# ST_SYS_Board_FPGA.net
KiCad netlist of a schematic drawn in Altium Designer
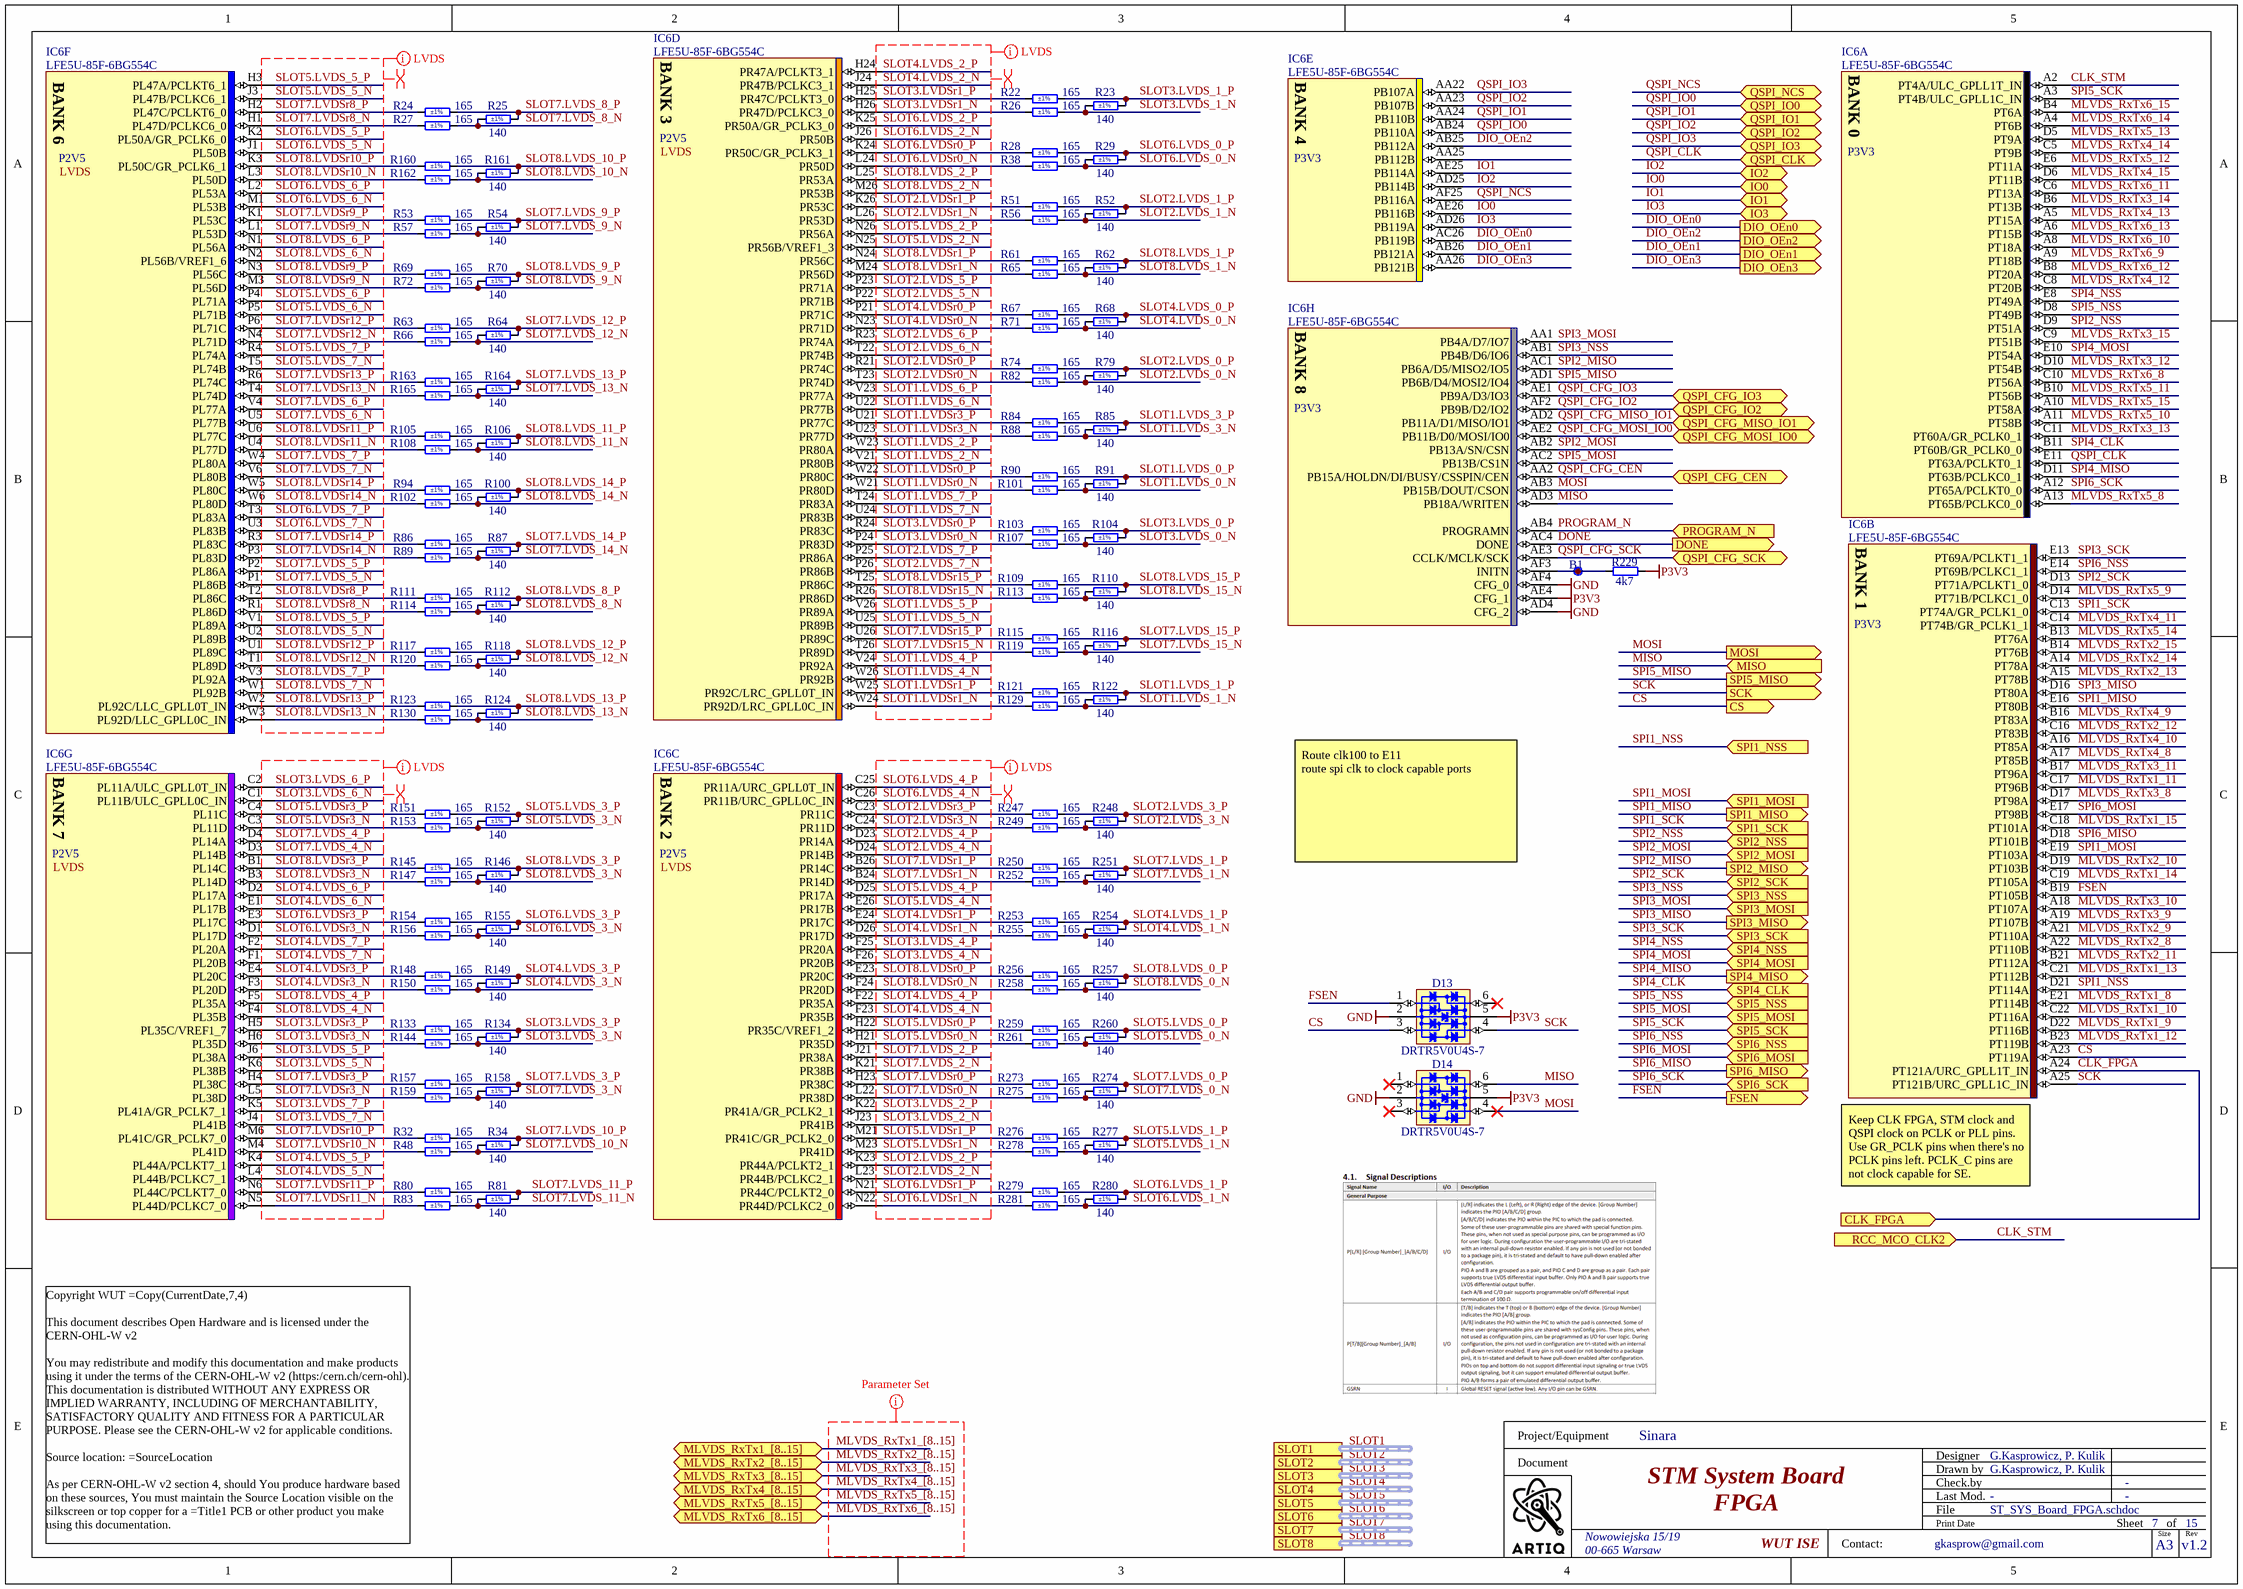
[diagram p0: ST_SYS_Board_FPGA.schdoc]

(export (version "E")
  (design (tool "Eeschema 10.0.6"))
  (components
    (comp (ref "B1")
      (value "SMD Pad")
      (footprint "C75")
      (description "Through Hole Pad")
      (fields (field (name "PART NUMBER") "SMD_PAD_D0.75MM") (field (name "AUTHOR") "CERN DEM BC"))
      (libsource (lib "Eletro-mechanical") (part "Single SMD Pad (Round)"))
    )
    (comp (ref "D13")
      (value "DRTR5V0U4S-7")
      (footprint "SOT65P210X110-6N")
      (description "Integrated Quad Ultra-Low Capacitance ESD Protection")
      (fields (field (name "MANUFACTURER") "DIODES") (field (name "AUTHOR") "GK"))
      (libsource (lib "Diodes") (part "D_TVS_DRTR5V0U4S-7"))
    )
    (comp (ref "D14")
      (value "DRTR5V0U4S-7")
      (footprint "SOT65P210X110-6N")
      (description "Integrated Quad Ultra-Low Capacitance ESD Protection")
      (fields (field (name "MANUFACTURER") "DIODES") (field (name "AUTHOR") "GK"))
      (libsource (lib "Diodes") (part "D_TVS_DRTR5V0U4S-7"))
    )
    (comp (ref "IC6")
      (value "LFE5U-85F-6BG554C")
      (footprint "BGA554C80P26X26_2300X2300X176")
      (fields (field (name "MANUFACTURER") "LATTICE SEMICONDUCTOR") (field (name "AUTHOR") "CERN DEM HF"))
      (libsource (lib "ICs And Semiconductors") (part "LFE5U-85F-6BG554C"))
    )
    (comp (ref "R22")
      (value "165")
      (footprint "RESC0603X28N")
      (description "Resistor - 1%")
      (fields
        (field (name "TOLERANCE") "±1%")
        (field (name "PART NUMBER") "R0201_165R_1%_0.05W_200PPM")
        (field (name "POWER") "0.05W")
        (field (name "AUTHOR") "CERN DEM MR")
      )
      (libsource (lib "Resistors") (part "Resistor - 1%"))
    )
    (comp (ref "R23")
      (value "140")
      (footprint "RESC0603X28N")
      (description "Resistor - 1%")
      (fields
        (field (name "TOLERANCE") "±1%")
        (field (name "PART NUMBER") "R0201_140R_1%_0.05W_200PPM")
        (field (name "POWER") "0.05W")
        (field (name "AUTHOR") "CERN DEM MR")
      )
      (libsource (lib "Resistors") (part "Resistor - 1%"))
    )
    (comp (ref "R24")
      (value "165")
      (footprint "RESC0603X28N")
      (description "Resistor - 1%")
      (fields
        (field (name "TOLERANCE") "±1%")
        (field (name "PART NUMBER") "R0201_165R_1%_0.05W_200PPM")
        (field (name "POWER") "0.05W")
        (field (name "AUTHOR") "CERN DEM MR")
      )
      (libsource (lib "Resistors") (part "Resistor - 1%"))
    )
    (comp (ref "R25")
      (value "140")
      (footprint "RESC0603X28N")
      (description "Resistor - 1%")
      (fields
        (field (name "TOLERANCE") "±1%")
        (field (name "PART NUMBER") "R0201_140R_1%_0.05W_200PPM")
        (field (name "POWER") "0.05W")
        (field (name "AUTHOR") "CERN DEM MR")
      )
      (libsource (lib "Resistors") (part "Resistor - 1%"))
    )
    (comp (ref "R26")
      (value "165")
      (footprint "RESC0603X28N")
      (description "Resistor - 1%")
      (fields
        (field (name "TOLERANCE") "±1%")
        (field (name "PART NUMBER") "R0201_165R_1%_0.05W_200PPM")
        (field (name "POWER") "0.05W")
        (field (name "AUTHOR") "CERN DEM MR")
      )
      (libsource (lib "Resistors") (part "Resistor - 1%"))
    )
    (comp (ref "R27")
      (value "165")
      (footprint "RESC0603X28N")
      (description "Resistor - 1%")
      (fields
        (field (name "TOLERANCE") "±1%")
        (field (name "PART NUMBER") "R0201_165R_1%_0.05W_200PPM")
        (field (name "POWER") "0.05W")
        (field (name "AUTHOR") "CERN DEM MR")
      )
      (libsource (lib "Resistors") (part "Resistor - 1%"))
    )
    (comp (ref "R28")
      (value "165")
      (footprint "RESC0603X28N")
      (description "Resistor - 1%")
      (fields
        (field (name "TOLERANCE") "±1%")
        (field (name "PART NUMBER") "R0201_165R_1%_0.05W_200PPM")
        (field (name "POWER") "0.05W")
        (field (name "AUTHOR") "CERN DEM MR")
      )
      (libsource (lib "Resistors") (part "Resistor - 1%"))
    )
    (comp (ref "R29")
      (value "140")
      (footprint "RESC0603X28N")
      (description "Resistor - 1%")
      (fields
        (field (name "TOLERANCE") "±1%")
        (field (name "PART NUMBER") "R0201_140R_1%_0.05W_200PPM")
        (field (name "POWER") "0.05W")
        (field (name "AUTHOR") "CERN DEM MR")
      )
      (libsource (lib "Resistors") (part "Resistor - 1%"))
    )
    (comp (ref "R32")
      (value "165")
      (footprint "RESC0603X28N")
      (description "Resistor - 1%")
      (fields
        (field (name "TOLERANCE") "±1%")
        (field (name "PART NUMBER") "R0201_165R_1%_0.05W_200PPM")
        (field (name "POWER") "0.05W")
        (field (name "AUTHOR") "CERN DEM MR")
      )
      (libsource (lib "Resistors") (part "Resistor - 1%"))
    )
    (comp (ref "R34")
      (value "140")
      (footprint "RESC0603X28N")
      (description "Resistor - 1%")
      (fields
        (field (name "TOLERANCE") "±1%")
        (field (name "PART NUMBER") "R0201_140R_1%_0.05W_200PPM")
        (field (name "POWER") "0.05W")
        (field (name "AUTHOR") "CERN DEM MR")
      )
      (libsource (lib "Resistors") (part "Resistor - 1%"))
    )
    (comp (ref "R38")
      (value "165")
      (footprint "RESC0603X28N")
      (description "Resistor - 1%")
      (fields
        (field (name "TOLERANCE") "±1%")
        (field (name "PART NUMBER") "R0201_165R_1%_0.05W_200PPM")
        (field (name "POWER") "0.05W")
        (field (name "AUTHOR") "CERN DEM MR")
      )
      (libsource (lib "Resistors") (part "Resistor - 1%"))
    )
    (comp (ref "R48")
      (value "165")
      (footprint "RESC0603X28N")
      (description "Resistor - 1%")
      (fields
        (field (name "TOLERANCE") "±1%")
        (field (name "PART NUMBER") "R0201_165R_1%_0.05W_200PPM")
        (field (name "POWER") "0.05W")
        (field (name "AUTHOR") "CERN DEM MR")
      )
      (libsource (lib "Resistors") (part "Resistor - 1%"))
    )
    (comp (ref "R51")
      (value "165")
      (footprint "RESC0603X28N")
      (description "Resistor - 1%")
      (fields
        (field (name "TOLERANCE") "±1%")
        (field (name "PART NUMBER") "R0201_165R_1%_0.05W_200PPM")
        (field (name "POWER") "0.05W")
        (field (name "AUTHOR") "CERN DEM MR")
      )
      (libsource (lib "Resistors") (part "Resistor - 1%"))
    )
    (comp (ref "R52")
      (value "140")
      (footprint "RESC0603X28N")
      (description "Resistor - 1%")
      (fields
        (field (name "TOLERANCE") "±1%")
        (field (name "PART NUMBER") "R0201_140R_1%_0.05W_200PPM")
        (field (name "POWER") "0.05W")
        (field (name "AUTHOR") "CERN DEM MR")
      )
      (libsource (lib "Resistors") (part "Resistor - 1%"))
    )
    (comp (ref "R53")
      (value "165")
      (footprint "RESC0603X28N")
      (description "Resistor - 1%")
      (fields
        (field (name "TOLERANCE") "±1%")
        (field (name "PART NUMBER") "R0201_165R_1%_0.05W_200PPM")
        (field (name "POWER") "0.05W")
        (field (name "AUTHOR") "CERN DEM MR")
      )
      (libsource (lib "Resistors") (part "Resistor - 1%"))
    )
    (comp (ref "R54")
      (value "140")
      (footprint "RESC0603X28N")
      (description "Resistor - 1%")
      (fields
        (field (name "TOLERANCE") "±1%")
        (field (name "PART NUMBER") "R0201_140R_1%_0.05W_200PPM")
        (field (name "POWER") "0.05W")
        (field (name "AUTHOR") "CERN DEM MR")
      )
      (libsource (lib "Resistors") (part "Resistor - 1%"))
    )
    (comp (ref "R56")
      (value "165")
      (footprint "RESC0603X28N")
      (description "Resistor - 1%")
      (fields
        (field (name "TOLERANCE") "±1%")
        (field (name "PART NUMBER") "R0201_165R_1%_0.05W_200PPM")
        (field (name "POWER") "0.05W")
        (field (name "AUTHOR") "CERN DEM MR")
      )
      (libsource (lib "Resistors") (part "Resistor - 1%"))
    )
    (comp (ref "R57")
      (value "165")
      (footprint "RESC0603X28N")
      (description "Resistor - 1%")
      (fields
        (field (name "TOLERANCE") "±1%")
        (field (name "PART NUMBER") "R0201_165R_1%_0.05W_200PPM")
        (field (name "POWER") "0.05W")
        (field (name "AUTHOR") "CERN DEM MR")
      )
      (libsource (lib "Resistors") (part "Resistor - 1%"))
    )
    (comp (ref "R61")
      (value "165")
      (footprint "RESC0603X28N")
      (description "Resistor - 1%")
      (fields
        (field (name "TOLERANCE") "±1%")
        (field (name "PART NUMBER") "R0201_165R_1%_0.05W_200PPM")
        (field (name "POWER") "0.05W")
        (field (name "AUTHOR") "CERN DEM MR")
      )
      (libsource (lib "Resistors") (part "Resistor - 1%"))
    )
    (comp (ref "R62")
      (value "140")
      (footprint "RESC0603X28N")
      (description "Resistor - 1%")
      (fields
        (field (name "TOLERANCE") "±1%")
        (field (name "PART NUMBER") "R0201_140R_1%_0.05W_200PPM")
        (field (name "POWER") "0.05W")
        (field (name "AUTHOR") "CERN DEM MR")
      )
      (libsource (lib "Resistors") (part "Resistor - 1%"))
    )
    (comp (ref "R63")
      (value "165")
      (footprint "RESC0603X28N")
      (description "Resistor - 1%")
      (fields
        (field (name "TOLERANCE") "±1%")
        (field (name "PART NUMBER") "R0201_165R_1%_0.05W_200PPM")
        (field (name "POWER") "0.05W")
        (field (name "AUTHOR") "CERN DEM MR")
      )
      (libsource (lib "Resistors") (part "Resistor - 1%"))
    )
    (comp (ref "R64")
      (value "140")
      (footprint "RESC0603X28N")
      (description "Resistor - 1%")
      (fields
        (field (name "TOLERANCE") "±1%")
        (field (name "PART NUMBER") "R0201_140R_1%_0.05W_200PPM")
        (field (name "POWER") "0.05W")
        (field (name "AUTHOR") "CERN DEM MR")
      )
      (libsource (lib "Resistors") (part "Resistor - 1%"))
    )
    (comp (ref "R65")
      (value "165")
      (footprint "RESC0603X28N")
      (description "Resistor - 1%")
      (fields
        (field (name "TOLERANCE") "±1%")
        (field (name "PART NUMBER") "R0201_165R_1%_0.05W_200PPM")
        (field (name "POWER") "0.05W")
        (field (name "AUTHOR") "CERN DEM MR")
      )
      (libsource (lib "Resistors") (part "Resistor - 1%"))
    )
    (comp (ref "R66")
      (value "165")
      (footprint "RESC0603X28N")
      (description "Resistor - 1%")
      (fields
        (field (name "TOLERANCE") "±1%")
        (field (name "PART NUMBER") "R0201_165R_1%_0.05W_200PPM")
        (field (name "POWER") "0.05W")
        (field (name "AUTHOR") "CERN DEM MR")
      )
      (libsource (lib "Resistors") (part "Resistor - 1%"))
    )
    (comp (ref "R67")
      (value "165")
      (footprint "RESC0603X28N")
      (description "Resistor - 1%")
      (fields
        (field (name "TOLERANCE") "±1%")
        (field (name "PART NUMBER") "R0201_165R_1%_0.05W_200PPM")
        (field (name "POWER") "0.05W")
        (field (name "AUTHOR") "CERN DEM MR")
      )
      (libsource (lib "Resistors") (part "Resistor - 1%"))
    )
    (comp (ref "R68")
      (value "140")
      (footprint "RESC0603X28N")
      (description "Resistor - 1%")
      (fields
        (field (name "TOLERANCE") "±1%")
        (field (name "PART NUMBER") "R0201_140R_1%_0.05W_200PPM")
        (field (name "POWER") "0.05W")
        (field (name "AUTHOR") "CERN DEM MR")
      )
      (libsource (lib "Resistors") (part "Resistor - 1%"))
    )
    (comp (ref "R69")
      (value "165")
      (footprint "RESC0603X28N")
      (description "Resistor - 1%")
      (fields
        (field (name "TOLERANCE") "±1%")
        (field (name "PART NUMBER") "R0201_165R_1%_0.05W_200PPM")
        (field (name "POWER") "0.05W")
        (field (name "AUTHOR") "CERN DEM MR")
      )
      (libsource (lib "Resistors") (part "Resistor - 1%"))
    )
    (comp (ref "R70")
      (value "140")
      (footprint "RESC0603X28N")
      (description "Resistor - 1%")
      (fields
        (field (name "TOLERANCE") "±1%")
        (field (name "PART NUMBER") "R0201_140R_1%_0.05W_200PPM")
        (field (name "POWER") "0.05W")
        (field (name "AUTHOR") "CERN DEM MR")
      )
      (libsource (lib "Resistors") (part "Resistor - 1%"))
    )
    (comp (ref "R71")
      (value "165")
      (footprint "RESC0603X28N")
      (description "Resistor - 1%")
      (fields
        (field (name "TOLERANCE") "±1%")
        (field (name "PART NUMBER") "R0201_165R_1%_0.05W_200PPM")
        (field (name "POWER") "0.05W")
        (field (name "AUTHOR") "CERN DEM MR")
      )
      (libsource (lib "Resistors") (part "Resistor - 1%"))
    )
    (comp (ref "R72")
      (value "165")
      (footprint "RESC0603X28N")
      (description "Resistor - 1%")
      (fields
        (field (name "TOLERANCE") "±1%")
        (field (name "PART NUMBER") "R0201_165R_1%_0.05W_200PPM")
        (field (name "POWER") "0.05W")
        (field (name "AUTHOR") "CERN DEM MR")
      )
      (libsource (lib "Resistors") (part "Resistor - 1%"))
    )
    (comp (ref "R74")
      (value "165")
      (footprint "RESC0603X28N")
      (description "Resistor - 1%")
      (fields
        (field (name "TOLERANCE") "±1%")
        (field (name "PART NUMBER") "R0201_165R_1%_0.05W_200PPM")
        (field (name "POWER") "0.05W")
        (field (name "AUTHOR") "CERN DEM MR")
      )
      (libsource (lib "Resistors") (part "Resistor - 1%"))
    )
    (comp (ref "R79")
      (value "140")
      (footprint "RESC0603X28N")
      (description "Resistor - 1%")
      (fields
        (field (name "TOLERANCE") "±1%")
        (field (name "PART NUMBER") "R0201_140R_1%_0.05W_200PPM")
        (field (name "POWER") "0.05W")
        (field (name "AUTHOR") "CERN DEM MR")
      )
      (libsource (lib "Resistors") (part "Resistor - 1%"))
    )
    (comp (ref "R80")
      (value "165")
      (footprint "RESC0603X28N")
      (description "Resistor - 1%")
      (fields
        (field (name "TOLERANCE") "±1%")
        (field (name "PART NUMBER") "R0201_165R_1%_0.05W_200PPM")
        (field (name "POWER") "0.05W")
        (field (name "AUTHOR") "CERN DEM MR")
      )
      (libsource (lib "Resistors") (part "Resistor - 1%"))
    )
    (comp (ref "R81")
      (value "140")
      (footprint "RESC0603X28N")
      (description "Resistor - 1%")
      (fields
        (field (name "TOLERANCE") "±1%")
        (field (name "PART NUMBER") "R0201_140R_1%_0.05W_200PPM")
        (field (name "POWER") "0.05W")
        (field (name "AUTHOR") "CERN DEM MR")
      )
      (libsource (lib "Resistors") (part "Resistor - 1%"))
    )
    (comp (ref "R82")
      (value "165")
      (footprint "RESC0603X28N")
      (description "Resistor - 1%")
      (fields
        (field (name "TOLERANCE") "±1%")
        (field (name "PART NUMBER") "R0201_165R_1%_0.05W_200PPM")
        (field (name "POWER") "0.05W")
        (field (name "AUTHOR") "CERN DEM MR")
      )
      (libsource (lib "Resistors") (part "Resistor - 1%"))
    )
    (comp (ref "R83")
      (value "165")
      (footprint "RESC0603X28N")
      (description "Resistor - 1%")
      (fields
        (field (name "TOLERANCE") "±1%")
        (field (name "PART NUMBER") "R0201_165R_1%_0.05W_200PPM")
        (field (name "POWER") "0.05W")
        (field (name "AUTHOR") "CERN DEM MR")
      )
      (libsource (lib "Resistors") (part "Resistor - 1%"))
    )
    (comp (ref "R84")
      (value "165")
      (footprint "RESC0603X28N")
      (description "Resistor - 1%")
      (fields
        (field (name "TOLERANCE") "±1%")
        (field (name "PART NUMBER") "R0201_165R_1%_0.05W_200PPM")
        (field (name "POWER") "0.05W")
        (field (name "AUTHOR") "CERN DEM MR")
      )
      (libsource (lib "Resistors") (part "Resistor - 1%"))
    )
    (comp (ref "R85")
      (value "140")
      (footprint "RESC0603X28N")
      (description "Resistor - 1%")
      (fields
        (field (name "TOLERANCE") "±1%")
        (field (name "PART NUMBER") "R0201_140R_1%_0.05W_200PPM")
        (field (name "POWER") "0.05W")
        (field (name "AUTHOR") "CERN DEM MR")
      )
      (libsource (lib "Resistors") (part "Resistor - 1%"))
    )
    (comp (ref "R86")
      (value "165")
      (footprint "RESC0603X28N")
      (description "Resistor - 1%")
      (fields
        (field (name "TOLERANCE") "±1%")
        (field (name "PART NUMBER") "R0201_165R_1%_0.05W_200PPM")
        (field (name "POWER") "0.05W")
        (field (name "AUTHOR") "CERN DEM MR")
      )
      (libsource (lib "Resistors") (part "Resistor - 1%"))
    )
    (comp (ref "R87")
      (value "140")
      (footprint "RESC0603X28N")
      (description "Resistor - 1%")
      (fields
        (field (name "TOLERANCE") "±1%")
        (field (name "PART NUMBER") "R0201_140R_1%_0.05W_200PPM")
        (field (name "POWER") "0.05W")
        (field (name "AUTHOR") "CERN DEM MR")
      )
      (libsource (lib "Resistors") (part "Resistor - 1%"))
    )
    (comp (ref "R88")
      (value "165")
      (footprint "RESC0603X28N")
      (description "Resistor - 1%")
      (fields
        (field (name "TOLERANCE") "±1%")
        (field (name "PART NUMBER") "R0201_165R_1%_0.05W_200PPM")
        (field (name "POWER") "0.05W")
        (field (name "AUTHOR") "CERN DEM MR")
      )
      (libsource (lib "Resistors") (part "Resistor - 1%"))
    )
    (comp (ref "R89")
      (value "165")
      (footprint "RESC0603X28N")
      (description "Resistor - 1%")
      (fields
        (field (name "TOLERANCE") "±1%")
        (field (name "PART NUMBER") "R0201_165R_1%_0.05W_200PPM")
        (field (name "POWER") "0.05W")
        (field (name "AUTHOR") "CERN DEM MR")
      )
      (libsource (lib "Resistors") (part "Resistor - 1%"))
    )
    (comp (ref "R90")
      (value "165")
      (footprint "RESC0603X28N")
      (description "Resistor - 1%")
      (fields
        (field (name "TOLERANCE") "±1%")
        (field (name "PART NUMBER") "R0201_165R_1%_0.05W_200PPM")
        (field (name "POWER") "0.05W")
        (field (name "AUTHOR") "CERN DEM MR")
      )
      (libsource (lib "Resistors") (part "Resistor - 1%"))
    )
    (comp (ref "R91")
      (value "140")
      (footprint "RESC0603X28N")
      (description "Resistor - 1%")
      (fields
        (field (name "TOLERANCE") "±1%")
        (field (name "PART NUMBER") "R0201_140R_1%_0.05W_200PPM")
        (field (name "POWER") "0.05W")
        (field (name "AUTHOR") "CERN DEM MR")
      )
      (libsource (lib "Resistors") (part "Resistor - 1%"))
    )
    (comp (ref "R94")
      (value "165")
      (footprint "RESC0603X28N")
      (description "Resistor - 1%")
      (fields
        (field (name "TOLERANCE") "±1%")
        (field (name "PART NUMBER") "R0201_165R_1%_0.05W_200PPM")
        (field (name "POWER") "0.05W")
        (field (name "AUTHOR") "CERN DEM MR")
      )
      (libsource (lib "Resistors") (part "Resistor - 1%"))
    )
    (comp (ref "R100")
      (value "140")
      (footprint "RESC0603X28N")
      (description "Resistor - 1%")
      (fields
        (field (name "TOLERANCE") "±1%")
        (field (name "PART NUMBER") "R0201_140R_1%_0.05W_200PPM")
        (field (name "POWER") "0.05W")
        (field (name "AUTHOR") "CERN DEM MR")
      )
      (libsource (lib "Resistors") (part "Resistor - 1%"))
    )
    (comp (ref "R101")
      (value "165")
      (footprint "RESC0603X28N")
      (description "Resistor - 1%")
      (fields
        (field (name "TOLERANCE") "±1%")
        (field (name "PART NUMBER") "R0201_165R_1%_0.05W_200PPM")
        (field (name "POWER") "0.05W")
        (field (name "AUTHOR") "CERN DEM MR")
      )
      (libsource (lib "Resistors") (part "Resistor - 1%"))
    )
    (comp (ref "R102")
      (value "165")
      (footprint "RESC0603X28N")
      (description "Resistor - 1%")
      (fields
        (field (name "TOLERANCE") "±1%")
        (field (name "PART NUMBER") "R0201_165R_1%_0.05W_200PPM")
        (field (name "POWER") "0.05W")
        (field (name "AUTHOR") "CERN DEM MR")
      )
      (libsource (lib "Resistors") (part "Resistor - 1%"))
    )
    (comp (ref "R103")
      (value "165")
      (footprint "RESC0603X28N")
      (description "Resistor - 1%")
      (fields
        (field (name "TOLERANCE") "±1%")
        (field (name "PART NUMBER") "R0201_165R_1%_0.05W_200PPM")
        (field (name "POWER") "0.05W")
        (field (name "AUTHOR") "CERN DEM MR")
      )
      (libsource (lib "Resistors") (part "Resistor - 1%"))
    )
    (comp (ref "R104")
      (value "140")
      (footprint "RESC0603X28N")
      (description "Resistor - 1%")
      (fields
        (field (name "TOLERANCE") "±1%")
        (field (name "PART NUMBER") "R0201_140R_1%_0.05W_200PPM")
        (field (name "POWER") "0.05W")
        (field (name "AUTHOR") "CERN DEM MR")
      )
      (libsource (lib "Resistors") (part "Resistor - 1%"))
    )
    (comp (ref "R105")
      (value "165")
      (footprint "RESC0603X28N")
      (description "Resistor - 1%")
      (fields
        (field (name "TOLERANCE") "±1%")
        (field (name "PART NUMBER") "R0201_165R_1%_0.05W_200PPM")
        (field (name "POWER") "0.05W")
        (field (name "AUTHOR") "CERN DEM MR")
      )
      (libsource (lib "Resistors") (part "Resistor - 1%"))
    )
    (comp (ref "R106")
      (value "140")
      (footprint "RESC0603X28N")
      (description "Resistor - 1%")
      (fields
        (field (name "TOLERANCE") "±1%")
        (field (name "PART NUMBER") "R0201_140R_1%_0.05W_200PPM")
        (field (name "POWER") "0.05W")
        (field (name "AUTHOR") "CERN DEM MR")
      )
      (libsource (lib "Resistors") (part "Resistor - 1%"))
    )
    (comp (ref "R107")
      (value "165")
      (footprint "RESC0603X28N")
      (description "Resistor - 1%")
      (fields
        (field (name "TOLERANCE") "±1%")
        (field (name "PART NUMBER") "R0201_165R_1%_0.05W_200PPM")
        (field (name "POWER") "0.05W")
        (field (name "AUTHOR") "CERN DEM MR")
      )
      (libsource (lib "Resistors") (part "Resistor - 1%"))
    )
    (comp (ref "R108")
      (value "165")
      (footprint "RESC0603X28N")
      (description "Resistor - 1%")
      (fields
        (field (name "TOLERANCE") "±1%")
        (field (name "PART NUMBER") "R0201_165R_1%_0.05W_200PPM")
        (field (name "POWER") "0.05W")
        (field (name "AUTHOR") "CERN DEM MR")
      )
      (libsource (lib "Resistors") (part "Resistor - 1%"))
    )
    (comp (ref "R109")
      (value "165")
      (footprint "RESC0603X28N")
      (description "Resistor - 1%")
      (fields
        (field (name "TOLERANCE") "±1%")
        (field (name "PART NUMBER") "R0201_165R_1%_0.05W_200PPM")
        (field (name "POWER") "0.05W")
        (field (name "AUTHOR") "CERN DEM MR")
      )
      (libsource (lib "Resistors") (part "Resistor - 1%"))
    )
    (comp (ref "R110")
      (value "140")
      (footprint "RESC0603X28N")
      (description "Resistor - 1%")
      (fields
        (field (name "TOLERANCE") "±1%")
        (field (name "PART NUMBER") "R0201_140R_1%_0.05W_200PPM")
        (field (name "POWER") "0.05W")
        (field (name "AUTHOR") "CERN DEM MR")
      )
      (libsource (lib "Resistors") (part "Resistor - 1%"))
    )
    (comp (ref "R111")
      (value "165")
      (footprint "RESC0603X28N")
      (description "Resistor - 1%")
      (fields
        (field (name "TOLERANCE") "±1%")
        (field (name "PART NUMBER") "R0201_165R_1%_0.05W_200PPM")
        (field (name "POWER") "0.05W")
        (field (name "AUTHOR") "CERN DEM MR")
      )
      (libsource (lib "Resistors") (part "Resistor - 1%"))
    )
    (comp (ref "R112")
      (value "140")
      (footprint "RESC0603X28N")
      (description "Resistor - 1%")
      (fields
        (field (name "TOLERANCE") "±1%")
        (field (name "PART NUMBER") "R0201_140R_1%_0.05W_200PPM")
        (field (name "POWER") "0.05W")
        (field (name "AUTHOR") "CERN DEM MR")
      )
      (libsource (lib "Resistors") (part "Resistor - 1%"))
    )
    (comp (ref "R113")
      (value "165")
      (footprint "RESC0603X28N")
      (description "Resistor - 1%")
      (fields
        (field (name "TOLERANCE") "±1%")
        (field (name "PART NUMBER") "R0201_165R_1%_0.05W_200PPM")
        (field (name "POWER") "0.05W")
        (field (name "AUTHOR") "CERN DEM MR")
      )
      (libsource (lib "Resistors") (part "Resistor - 1%"))
    )
    (comp (ref "R114")
      (value "165")
      (footprint "RESC0603X28N")
      (description "Resistor - 1%")
      (fields
        (field (name "TOLERANCE") "±1%")
        (field (name "PART NUMBER") "R0201_165R_1%_0.05W_200PPM")
        (field (name "POWER") "0.05W")
        (field (name "AUTHOR") "CERN DEM MR")
      )
      (libsource (lib "Resistors") (part "Resistor - 1%"))
    )
    (comp (ref "R115")
      (value "165")
      (footprint "RESC0603X28N")
      (description "Resistor - 1%")
      (fields
        (field (name "TOLERANCE") "±1%")
        (field (name "PART NUMBER") "R0201_165R_1%_0.05W_200PPM")
        (field (name "POWER") "0.05W")
        (field (name "AUTHOR") "CERN DEM MR")
      )
      (libsource (lib "Resistors") (part "Resistor - 1%"))
    )
    (comp (ref "R116")
      (value "140")
      (footprint "RESC0603X28N")
      (description "Resistor - 1%")
      (fields
        (field (name "TOLERANCE") "±1%")
        (field (name "PART NUMBER") "R0201_140R_1%_0.05W_200PPM")
        (field (name "POWER") "0.05W")
        (field (name "AUTHOR") "CERN DEM MR")
      )
      (libsource (lib "Resistors") (part "Resistor - 1%"))
    )
    (comp (ref "R117")
      (value "165")
      (footprint "RESC0603X28N")
      (description "Resistor - 1%")
      (fields
        (field (name "TOLERANCE") "±1%")
        (field (name "PART NUMBER") "R0201_165R_1%_0.05W_200PPM")
        (field (name "POWER") "0.05W")
        (field (name "AUTHOR") "CERN DEM MR")
      )
      (libsource (lib "Resistors") (part "Resistor - 1%"))
    )
    (comp (ref "R118")
      (value "140")
      (footprint "RESC0603X28N")
      (description "Resistor - 1%")
      (fields
        (field (name "TOLERANCE") "±1%")
        (field (name "PART NUMBER") "R0201_140R_1%_0.05W_200PPM")
        (field (name "POWER") "0.05W")
        (field (name "AUTHOR") "CERN DEM MR")
      )
      (libsource (lib "Resistors") (part "Resistor - 1%"))
    )
    (comp (ref "R119")
      (value "165")
      (footprint "RESC0603X28N")
      (description "Resistor - 1%")
      (fields
        (field (name "TOLERANCE") "±1%")
        (field (name "PART NUMBER") "R0201_165R_1%_0.05W_200PPM")
        (field (name "POWER") "0.05W")
        (field (name "AUTHOR") "CERN DEM MR")
      )
      (libsource (lib "Resistors") (part "Resistor - 1%"))
    )
    (comp (ref "R120")
      (value "165")
      (footprint "RESC0603X28N")
      (description "Resistor - 1%")
      (fields
        (field (name "TOLERANCE") "±1%")
        (field (name "PART NUMBER") "R0201_165R_1%_0.05W_200PPM")
        (field (name "POWER") "0.05W")
        (field (name "AUTHOR") "CERN DEM MR")
      )
      (libsource (lib "Resistors") (part "Resistor - 1%"))
    )
    (comp (ref "R121")
      (value "165")
      (footprint "RESC0603X28N")
      (description "Resistor - 1%")
      (fields
        (field (name "TOLERANCE") "±1%")
        (field (name "PART NUMBER") "R0201_165R_1%_0.05W_200PPM")
        (field (name "POWER") "0.05W")
        (field (name "AUTHOR") "CERN DEM MR")
      )
      (libsource (lib "Resistors") (part "Resistor - 1%"))
    )
    (comp (ref "R122")
      (value "140")
      (footprint "RESC0603X28N")
      (description "Resistor - 1%")
      (fields
        (field (name "TOLERANCE") "±1%")
        (field (name "PART NUMBER") "R0201_140R_1%_0.05W_200PPM")
        (field (name "POWER") "0.05W")
        (field (name "AUTHOR") "CERN DEM MR")
      )
      (libsource (lib "Resistors") (part "Resistor - 1%"))
    )
    (comp (ref "R123")
      (value "165")
      (footprint "RESC0603X28N")
      (description "Resistor - 1%")
      (fields
        (field (name "TOLERANCE") "±1%")
        (field (name "PART NUMBER") "R0201_165R_1%_0.05W_200PPM")
        (field (name "POWER") "0.05W")
        (field (name "AUTHOR") "CERN DEM MR")
      )
      (libsource (lib "Resistors") (part "Resistor - 1%"))
    )
    (comp (ref "R124")
      (value "140")
      (footprint "RESC0603X28N")
      (description "Resistor - 1%")
      (fields
        (field (name "TOLERANCE") "±1%")
        (field (name "PART NUMBER") "R0201_140R_1%_0.05W_200PPM")
        (field (name "POWER") "0.05W")
        (field (name "AUTHOR") "CERN DEM MR")
      )
      (libsource (lib "Resistors") (part "Resistor - 1%"))
    )
    (comp (ref "R129")
      (value "165")
      (footprint "RESC0603X28N")
      (description "Resistor - 1%")
      (fields
        (field (name "TOLERANCE") "±1%")
        (field (name "PART NUMBER") "R0201_165R_1%_0.05W_200PPM")
        (field (name "POWER") "0.05W")
        (field (name "AUTHOR") "CERN DEM MR")
      )
      (libsource (lib "Resistors") (part "Resistor - 1%"))
    )
    (comp (ref "R130")
      (value "165")
      (footprint "RESC0603X28N")
      (description "Resistor - 1%")
      (fields
        (field (name "TOLERANCE") "±1%")
        (field (name "PART NUMBER") "R0201_165R_1%_0.05W_200PPM")
        (field (name "POWER") "0.05W")
        (field (name "AUTHOR") "CERN DEM MR")
      )
      (libsource (lib "Resistors") (part "Resistor - 1%"))
    )
    (comp (ref "R133")
      (value "165")
      (footprint "RESC0603X28N")
      (description "Resistor - 1%")
      (fields
        (field (name "TOLERANCE") "±1%")
        (field (name "PART NUMBER") "R0201_165R_1%_0.05W_200PPM")
        (field (name "POWER") "0.05W")
        (field (name "AUTHOR") "CERN DEM MR")
      )
      (libsource (lib "Resistors") (part "Resistor - 1%"))
    )
    (comp (ref "R134")
      (value "140")
      (footprint "RESC0603X28N")
      (description "Resistor - 1%")
      (fields
        (field (name "TOLERANCE") "±1%")
        (field (name "PART NUMBER") "R0201_140R_1%_0.05W_200PPM")
        (field (name "POWER") "0.05W")
        (field (name "AUTHOR") "CERN DEM MR")
      )
      (libsource (lib "Resistors") (part "Resistor - 1%"))
    )
    (comp (ref "R144")
      (value "165")
      (footprint "RESC0603X28N")
      (description "Resistor - 1%")
      (fields
        (field (name "TOLERANCE") "±1%")
        (field (name "PART NUMBER") "R0201_165R_1%_0.05W_200PPM")
        (field (name "POWER") "0.05W")
        (field (name "AUTHOR") "CERN DEM MR")
      )
      (libsource (lib "Resistors") (part "Resistor - 1%"))
    )
    (comp (ref "R145")
      (value "165")
      (footprint "RESC0603X28N")
      (description "Resistor - 1%")
      (fields
        (field (name "TOLERANCE") "±1%")
        (field (name "PART NUMBER") "R0201_165R_1%_0.05W_200PPM")
        (field (name "POWER") "0.05W")
        (field (name "AUTHOR") "CERN DEM MR")
      )
      (libsource (lib "Resistors") (part "Resistor - 1%"))
    )
    (comp (ref "R146")
      (value "140")
      (footprint "RESC0603X28N")
      (description "Resistor - 1%")
      (fields
        (field (name "TOLERANCE") "±1%")
        (field (name "PART NUMBER") "R0201_140R_1%_0.05W_200PPM")
        (field (name "POWER") "0.05W")
        (field (name "AUTHOR") "CERN DEM MR")
      )
      (libsource (lib "Resistors") (part "Resistor - 1%"))
    )
    (comp (ref "R147")
      (value "165")
      (footprint "RESC0603X28N")
      (description "Resistor - 1%")
      (fields
        (field (name "TOLERANCE") "±1%")
        (field (name "PART NUMBER") "R0201_165R_1%_0.05W_200PPM")
        (field (name "POWER") "0.05W")
        (field (name "AUTHOR") "CERN DEM MR")
      )
      (libsource (lib "Resistors") (part "Resistor - 1%"))
    )
    (comp (ref "R148")
      (value "165")
      (footprint "RESC0603X28N")
      (description "Resistor - 1%")
      (fields
        (field (name "TOLERANCE") "±1%")
        (field (name "PART NUMBER") "R0201_165R_1%_0.05W_200PPM")
        (field (name "POWER") "0.05W")
        (field (name "AUTHOR") "CERN DEM MR")
      )
      (libsource (lib "Resistors") (part "Resistor - 1%"))
    )
    (comp (ref "R149")
      (value "140")
      (footprint "RESC0603X28N")
      (description "Resistor - 1%")
      (fields
        (field (name "TOLERANCE") "±1%")
        (field (name "PART NUMBER") "R0201_140R_1%_0.05W_200PPM")
        (field (name "POWER") "0.05W")
        (field (name "AUTHOR") "CERN DEM MR")
      )
      (libsource (lib "Resistors") (part "Resistor - 1%"))
    )
    (comp (ref "R150")
      (value "165")
      (footprint "RESC0603X28N")
      (description "Resistor - 1%")
      (fields
        (field (name "TOLERANCE") "±1%")
        (field (name "PART NUMBER") "R0201_165R_1%_0.05W_200PPM")
        (field (name "POWER") "0.05W")
        (field (name "AUTHOR") "CERN DEM MR")
      )
      (libsource (lib "Resistors") (part "Resistor - 1%"))
    )
    (comp (ref "R151")
      (value "165")
      (footprint "RESC0603X28N")
      (description "Resistor - 1%")
      (fields
        (field (name "TOLERANCE") "±1%")
        (field (name "PART NUMBER") "R0201_165R_1%_0.05W_200PPM")
        (field (name "POWER") "0.05W")
        (field (name "AUTHOR") "CERN DEM MR")
      )
      (libsource (lib "Resistors") (part "Resistor - 1%"))
    )
    (comp (ref "R152")
      (value "140")
      (footprint "RESC0603X28N")
      (description "Resistor - 1%")
      (fields
        (field (name "TOLERANCE") "±1%")
        (field (name "PART NUMBER") "R0201_140R_1%_0.05W_200PPM")
        (field (name "POWER") "0.05W")
        (field (name "AUTHOR") "CERN DEM MR")
      )
      (libsource (lib "Resistors") (part "Resistor - 1%"))
    )
    (comp (ref "R153")
      (value "165")
      (footprint "RESC0603X28N")
      (description "Resistor - 1%")
      (fields
        (field (name "TOLERANCE") "±1%")
        (field (name "PART NUMBER") "R0201_165R_1%_0.05W_200PPM")
        (field (name "POWER") "0.05W")
        (field (name "AUTHOR") "CERN DEM MR")
      )
      (libsource (lib "Resistors") (part "Resistor - 1%"))
    )
    (comp (ref "R154")
      (value "165")
      (footprint "RESC0603X28N")
      (description "Resistor - 1%")
      (fields
        (field (name "TOLERANCE") "±1%")
        (field (name "PART NUMBER") "R0201_165R_1%_0.05W_200PPM")
        (field (name "POWER") "0.05W")
        (field (name "AUTHOR") "CERN DEM MR")
      )
      (libsource (lib "Resistors") (part "Resistor - 1%"))
    )
    (comp (ref "R155")
      (value "140")
      (footprint "RESC0603X28N")
      (description "Resistor - 1%")
      (fields
        (field (name "TOLERANCE") "±1%")
        (field (name "PART NUMBER") "R0201_140R_1%_0.05W_200PPM")
        (field (name "POWER") "0.05W")
        (field (name "AUTHOR") "CERN DEM MR")
      )
      (libsource (lib "Resistors") (part "Resistor - 1%"))
    )
    (comp (ref "R156")
      (value "165")
      (footprint "RESC0603X28N")
      (description "Resistor - 1%")
      (fields
        (field (name "TOLERANCE") "±1%")
        (field (name "PART NUMBER") "R0201_165R_1%_0.05W_200PPM")
        (field (name "POWER") "0.05W")
        (field (name "AUTHOR") "CERN DEM MR")
      )
      (libsource (lib "Resistors") (part "Resistor - 1%"))
    )
    (comp (ref "R157")
      (value "165")
      (footprint "RESC0603X28N")
      (description "Resistor - 1%")
      (fields
        (field (name "TOLERANCE") "±1%")
        (field (name "PART NUMBER") "R0201_165R_1%_0.05W_200PPM")
        (field (name "POWER") "0.05W")
        (field (name "AUTHOR") "CERN DEM MR")
      )
      (libsource (lib "Resistors") (part "Resistor - 1%"))
    )
    (comp (ref "R158")
      (value "140")
      (footprint "RESC0603X28N")
      (description "Resistor - 1%")
      (fields
        (field (name "TOLERANCE") "±1%")
        (field (name "PART NUMBER") "R0201_140R_1%_0.05W_200PPM")
        (field (name "POWER") "0.05W")
        (field (name "AUTHOR") "CERN DEM MR")
      )
      (libsource (lib "Resistors") (part "Resistor - 1%"))
    )
    (comp (ref "R159")
      (value "165")
      (footprint "RESC0603X28N")
      (description "Resistor - 1%")
      (fields
        (field (name "TOLERANCE") "±1%")
        (field (name "PART NUMBER") "R0201_165R_1%_0.05W_200PPM")
        (field (name "POWER") "0.05W")
        (field (name "AUTHOR") "CERN DEM MR")
      )
      (libsource (lib "Resistors") (part "Resistor - 1%"))
    )
    (comp (ref "R160")
      (value "165")
      (footprint "RESC0603X28N")
      (description "Resistor - 1%")
      (fields
        (field (name "TOLERANCE") "±1%")
        (field (name "PART NUMBER") "R0201_165R_1%_0.05W_200PPM")
        (field (name "POWER") "0.05W")
        (field (name "AUTHOR") "CERN DEM MR")
      )
      (libsource (lib "Resistors") (part "Resistor - 1%"))
    )
    (comp (ref "R161")
      (value "140")
      (footprint "RESC0603X28N")
      (description "Resistor - 1%")
      (fields
        (field (name "TOLERANCE") "±1%")
        (field (name "PART NUMBER") "R0201_140R_1%_0.05W_200PPM")
        (field (name "POWER") "0.05W")
        (field (name "AUTHOR") "CERN DEM MR")
      )
      (libsource (lib "Resistors") (part "Resistor - 1%"))
    )
    (comp (ref "R162")
      (value "165")
      (footprint "RESC0603X28N")
      (description "Resistor - 1%")
      (fields
        (field (name "TOLERANCE") "±1%")
        (field (name "PART NUMBER") "R0201_165R_1%_0.05W_200PPM")
        (field (name "POWER") "0.05W")
        (field (name "AUTHOR") "CERN DEM MR")
      )
      (libsource (lib "Resistors") (part "Resistor - 1%"))
    )
    (comp (ref "R163")
      (value "165")
      (footprint "RESC0603X28N")
      (description "Resistor - 1%")
      (fields
        (field (name "TOLERANCE") "±1%")
        (field (name "PART NUMBER") "R0201_165R_1%_0.05W_200PPM")
        (field (name "POWER") "0.05W")
        (field (name "AUTHOR") "CERN DEM MR")
      )
      (libsource (lib "Resistors") (part "Resistor - 1%"))
    )
    (comp (ref "R164")
      (value "140")
      (footprint "RESC0603X28N")
      (description "Resistor - 1%")
      (fields
        (field (name "TOLERANCE") "±1%")
        (field (name "PART NUMBER") "R0201_140R_1%_0.05W_200PPM")
        (field (name "POWER") "0.05W")
        (field (name "AUTHOR") "CERN DEM MR")
      )
      (libsource (lib "Resistors") (part "Resistor - 1%"))
    )
    (comp (ref "R165")
      (value "165")
      (footprint "RESC0603X28N")
      (description "Resistor - 1%")
      (fields
        (field (name "TOLERANCE") "±1%")
        (field (name "PART NUMBER") "R0201_165R_1%_0.05W_200PPM")
        (field (name "POWER") "0.05W")
        (field (name "AUTHOR") "CERN DEM MR")
      )
      (libsource (lib "Resistors") (part "Resistor - 1%"))
    )
    (comp (ref "R229")
      (value "4k7")
      (footprint "RESC1005X40N")
      (description "Resistor - 1%")
      (fields
        (field (name "PART NUMBER") "R0402_4K7_1%_0.0625W_100PPM")
        (field (name "POWER") "0.0625W")
        (field (name "AUTHOR") "CERN DEM JLC")
      )
      (libsource (lib "Resistors") (part "Resistor - 1%"))
    )
    (comp (ref "R247")
      (value "165")
      (footprint "RESC0603X28N")
      (description "Resistor - 1%")
      (fields
        (field (name "TOLERANCE") "±1%")
        (field (name "PART NUMBER") "R0201_165R_1%_0.05W_200PPM")
        (field (name "POWER") "0.05W")
        (field (name "AUTHOR") "CERN DEM MR")
      )
      (libsource (lib "Resistors") (part "Resistor - 1%"))
    )
    (comp (ref "R248")
      (value "140")
      (footprint "RESC0603X28N")
      (description "Resistor - 1%")
      (fields
        (field (name "TOLERANCE") "±1%")
        (field (name "PART NUMBER") "R0201_140R_1%_0.05W_200PPM")
        (field (name "POWER") "0.05W")
        (field (name "AUTHOR") "CERN DEM MR")
      )
      (libsource (lib "Resistors") (part "Resistor - 1%"))
    )
    (comp (ref "R249")
      (value "165")
      (footprint "RESC0603X28N")
      (description "Resistor - 1%")
      (fields
        (field (name "TOLERANCE") "±1%")
        (field (name "PART NUMBER") "R0201_165R_1%_0.05W_200PPM")
        (field (name "POWER") "0.05W")
        (field (name "AUTHOR") "CERN DEM MR")
      )
      (libsource (lib "Resistors") (part "Resistor - 1%"))
    )
    (comp (ref "R250")
      (value "165")
      (footprint "RESC0603X28N")
      (description "Resistor - 1%")
      (fields
        (field (name "TOLERANCE") "±1%")
        (field (name "PART NUMBER") "R0201_165R_1%_0.05W_200PPM")
        (field (name "POWER") "0.05W")
        (field (name "AUTHOR") "CERN DEM MR")
      )
      (libsource (lib "Resistors") (part "Resistor - 1%"))
    )
    (comp (ref "R251")
      (value "140")
      (footprint "RESC0603X28N")
      (description "Resistor - 1%")
      (fields
        (field (name "TOLERANCE") "±1%")
        (field (name "PART NUMBER") "R0201_140R_1%_0.05W_200PPM")
        (field (name "POWER") "0.05W")
        (field (name "AUTHOR") "CERN DEM MR")
      )
      (libsource (lib "Resistors") (part "Resistor - 1%"))
    )
    (comp (ref "R252")
      (value "165")
      (footprint "RESC0603X28N")
      (description "Resistor - 1%")
      (fields
        (field (name "TOLERANCE") "±1%")
        (field (name "PART NUMBER") "R0201_165R_1%_0.05W_200PPM")
        (field (name "POWER") "0.05W")
        (field (name "AUTHOR") "CERN DEM MR")
      )
      (libsource (lib "Resistors") (part "Resistor - 1%"))
    )
    (comp (ref "R253")
      (value "165")
      (footprint "RESC0603X28N")
      (description "Resistor - 1%")
      (fields
        (field (name "TOLERANCE") "±1%")
        (field (name "PART NUMBER") "R0201_165R_1%_0.05W_200PPM")
        (field (name "POWER") "0.05W")
        (field (name "AUTHOR") "CERN DEM MR")
      )
      (libsource (lib "Resistors") (part "Resistor - 1%"))
    )
    (comp (ref "R254")
      (value "140")
      (footprint "RESC0603X28N")
      (description "Resistor - 1%")
      (fields
        (field (name "TOLERANCE") "±1%")
        (field (name "PART NUMBER") "R0201_140R_1%_0.05W_200PPM")
        (field (name "POWER") "0.05W")
        (field (name "AUTHOR") "CERN DEM MR")
      )
      (libsource (lib "Resistors") (part "Resistor - 1%"))
    )
    (comp (ref "R255")
      (value "165")
      (footprint "RESC0603X28N")
      (description "Resistor - 1%")
      (fields
        (field (name "TOLERANCE") "±1%")
        (field (name "PART NUMBER") "R0201_165R_1%_0.05W_200PPM")
        (field (name "POWER") "0.05W")
        (field (name "AUTHOR") "CERN DEM MR")
      )
      (libsource (lib "Resistors") (part "Resistor - 1%"))
    )
    (comp (ref "R256")
      (value "165")
      (footprint "RESC0603X28N")
      (description "Resistor - 1%")
      (fields
        (field (name "TOLERANCE") "±1%")
        (field (name "PART NUMBER") "R0201_165R_1%_0.05W_200PPM")
        (field (name "POWER") "0.05W")
        (field (name "AUTHOR") "CERN DEM MR")
      )
      (libsource (lib "Resistors") (part "Resistor - 1%"))
    )
    (comp (ref "R257")
      (value "140")
      (footprint "RESC0603X28N")
      (description "Resistor - 1%")
      (fields
        (field (name "TOLERANCE") "±1%")
        (field (name "PART NUMBER") "R0201_140R_1%_0.05W_200PPM")
        (field (name "POWER") "0.05W")
        (field (name "AUTHOR") "CERN DEM MR")
      )
      (libsource (lib "Resistors") (part "Resistor - 1%"))
    )
    (comp (ref "R258")
      (value "165")
      (footprint "RESC0603X28N")
      (description "Resistor - 1%")
      (fields
        (field (name "TOLERANCE") "±1%")
        (field (name "PART NUMBER") "R0201_165R_1%_0.05W_200PPM")
        (field (name "POWER") "0.05W")
        (field (name "AUTHOR") "CERN DEM MR")
      )
      (libsource (lib "Resistors") (part "Resistor - 1%"))
    )
    (comp (ref "R259")
      (value "165")
      (footprint "RESC0603X28N")
      (description "Resistor - 1%")
      (fields
        (field (name "TOLERANCE") "±1%")
        (field (name "PART NUMBER") "R0201_165R_1%_0.05W_200PPM")
        (field (name "POWER") "0.05W")
        (field (name "AUTHOR") "CERN DEM MR")
      )
      (libsource (lib "Resistors") (part "Resistor - 1%"))
    )
    (comp (ref "R260")
      (value "140")
      (footprint "RESC0603X28N")
      (description "Resistor - 1%")
      (fields
        (field (name "TOLERANCE") "±1%")
        (field (name "PART NUMBER") "R0201_140R_1%_0.05W_200PPM")
        (field (name "POWER") "0.05W")
        (field (name "AUTHOR") "CERN DEM MR")
      )
      (libsource (lib "Resistors") (part "Resistor - 1%"))
    )
    (comp (ref "R261")
      (value "165")
      (footprint "RESC0603X28N")
      (description "Resistor - 1%")
      (fields
        (field (name "TOLERANCE") "±1%")
        (field (name "PART NUMBER") "R0201_165R_1%_0.05W_200PPM")
        (field (name "POWER") "0.05W")
        (field (name "AUTHOR") "CERN DEM MR")
      )
      (libsource (lib "Resistors") (part "Resistor - 1%"))
    )
    (comp (ref "R273")
      (value "165")
      (footprint "RESC0603X28N")
      (description "Resistor - 1%")
      (fields
        (field (name "TOLERANCE") "±1%")
        (field (name "PART NUMBER") "R0201_165R_1%_0.05W_200PPM")
        (field (name "POWER") "0.05W")
        (field (name "AUTHOR") "CERN DEM MR")
      )
      (libsource (lib "Resistors") (part "Resistor - 1%"))
    )
    (comp (ref "R274")
      (value "140")
      (footprint "RESC0603X28N")
      (description "Resistor - 1%")
      (fields
        (field (name "TOLERANCE") "±1%")
        (field (name "PART NUMBER") "R0201_140R_1%_0.05W_200PPM")
        (field (name "POWER") "0.05W")
        (field (name "AUTHOR") "CERN DEM MR")
      )
      (libsource (lib "Resistors") (part "Resistor - 1%"))
    )
    (comp (ref "R275")
      (value "165")
      (footprint "RESC0603X28N")
      (description "Resistor - 1%")
      (fields
        (field (name "TOLERANCE") "±1%")
        (field (name "PART NUMBER") "R0201_165R_1%_0.05W_200PPM")
        (field (name "POWER") "0.05W")
        (field (name "AUTHOR") "CERN DEM MR")
      )
      (libsource (lib "Resistors") (part "Resistor - 1%"))
    )
    (comp (ref "R276")
      (value "165")
      (footprint "RESC0603X28N")
      (description "Resistor - 1%")
      (fields
        (field (name "TOLERANCE") "±1%")
        (field (name "PART NUMBER") "R0201_165R_1%_0.05W_200PPM")
        (field (name "POWER") "0.05W")
        (field (name "AUTHOR") "CERN DEM MR")
      )
      (libsource (lib "Resistors") (part "Resistor - 1%"))
    )
    (comp (ref "R277")
      (value "140")
      (footprint "RESC0603X28N")
      (description "Resistor - 1%")
      (fields
        (field (name "TOLERANCE") "±1%")
        (field (name "PART NUMBER") "R0201_140R_1%_0.05W_200PPM")
        (field (name "POWER") "0.05W")
        (field (name "AUTHOR") "CERN DEM MR")
      )
      (libsource (lib "Resistors") (part "Resistor - 1%"))
    )
    (comp (ref "R278")
      (value "165")
      (footprint "RESC0603X28N")
      (description "Resistor - 1%")
      (fields
        (field (name "TOLERANCE") "±1%")
        (field (name "PART NUMBER") "R0201_165R_1%_0.05W_200PPM")
        (field (name "POWER") "0.05W")
        (field (name "AUTHOR") "CERN DEM MR")
      )
      (libsource (lib "Resistors") (part "Resistor - 1%"))
    )
    (comp (ref "R279")
      (value "165")
      (footprint "RESC0603X28N")
      (description "Resistor - 1%")
      (fields
        (field (name "TOLERANCE") "±1%")
        (field (name "PART NUMBER") "R0201_165R_1%_0.05W_200PPM")
        (field (name "POWER") "0.05W")
        (field (name "AUTHOR") "CERN DEM MR")
      )
      (libsource (lib "Resistors") (part "Resistor - 1%"))
    )
    (comp (ref "R280")
      (value "140")
      (footprint "RESC0603X28N")
      (description "Resistor - 1%")
      (fields
        (field (name "TOLERANCE") "±1%")
        (field (name "PART NUMBER") "R0201_140R_1%_0.05W_200PPM")
        (field (name "POWER") "0.05W")
        (field (name "AUTHOR") "CERN DEM MR")
      )
      (libsource (lib "Resistors") (part "Resistor - 1%"))
    )
    (comp (ref "R281")
      (value "165")
      (footprint "RESC0603X28N")
      (description "Resistor - 1%")
      (fields
        (field (name "TOLERANCE") "±1%")
        (field (name "PART NUMBER") "R0201_165R_1%_0.05W_200PPM")
        (field (name "POWER") "0.05W")
        (field (name "AUTHOR") "CERN DEM MR")
      )
      (libsource (lib "Resistors") (part "Resistor - 1%"))
    )
  )
  (nets
    (net (code "9") (name "/CLK_FPGA") (class "Default")
      (node (ref "IC6") (pin "A24") (pinfunction "PT121A/URC_GPLL1T_IN_A24") (pintype "bidirectional"))
    )
    (net (code "10") (name "/CLK_STM") (class "Default")
      (node (ref "IC6") (pin "A2") (pinfunction "PT4A/ULC_GPLL1T_IN_A2") (pintype "bidirectional"))
    )
    (net (code "11") (name "/CS") (class "Default")
      (node (ref "D13") (pin "3") (pinfunction "I/O2_3") (pintype "bidirectional"))
      (node (ref "IC6") (pin "A23") (pinfunction "PT119A_A23") (pintype "bidirectional"))
    )
    (net (code "12") (name "/DIO_OEn0") (class "Default")
      (node (ref "IC6") (pin "AC26") (pinfunction "PB119B_AC26") (pintype "bidirectional"))
    )
    (net (code "13") (name "/DIO_OEn1") (class "Default")
      (node (ref "IC6") (pin "AB26") (pinfunction "PB121A_AB26") (pintype "bidirectional"))
    )
    (net (code "14") (name "/DIO_OEn2") (class "Default")
      (node (ref "IC6") (pin "AB25") (pinfunction "PB112A_AB25") (pintype "bidirectional"))
    )
    (net (code "15") (name "/DIO_OEn3") (class "Default")
      (node (ref "IC6") (pin "AA26") (pinfunction "PB121B_AA26") (pintype "bidirectional"))
    )
    (net (code "16") (name "/DONE") (class "Default")
      (node (ref "IC6") (pin "AC4") (pinfunction "DONE_AC4") (pintype "bidirectional"))
    )
    (net (code "17") (name "/FSEN") (class "Default")
      (node (ref "D13") (pin "1") (pinfunction "I/O1_1") (pintype "bidirectional"))
      (node (ref "IC6") (pin "B19") (pinfunction "PT105B_B19") (pintype "bidirectional"))
    )
    (net (code "18") (name "/IO0") (class "Default")
      (node (ref "IC6") (pin "AE26") (pinfunction "PB116B_AE26") (pintype "bidirectional"))
    )
    (net (code "19") (name "/IO1") (class "Default")
      (node (ref "IC6") (pin "AE25") (pinfunction "PB114A_AE25") (pintype "bidirectional"))
    )
    (net (code "20") (name "/IO2") (class "Default")
      (node (ref "IC6") (pin "AD25") (pinfunction "PB114B_AD25") (pintype "bidirectional"))
    )
    (net (code "21") (name "/IO3") (class "Default")
      (node (ref "IC6") (pin "AD26") (pinfunction "PB119A_AD26") (pintype "bidirectional"))
    )
    (net (code "22") (name "/MISO") (class "Default")
      (node (ref "D14") (pin "6") (pinfunction "I/O4_6") (pintype "bidirectional"))
      (node (ref "IC6") (pin "AD3") (pinfunction "PB18A/WRITEN_AD3") (pintype "bidirectional"))
    )
    (net (code "23") (name "/MLVDS_RxTx1_8") (class "Default")
      (node (ref "IC6") (pin "E21") (pinfunction "PT114B_E21") (pintype "bidirectional"))
    )
    (net (code "24") (name "/MLVDS_RxTx1_9") (class "Default")
      (node (ref "IC6") (pin "D22") (pinfunction "PT116B_D22") (pintype "bidirectional"))
    )
    (net (code "25") (name "/MLVDS_RxTx1_10") (class "Default")
      (node (ref "IC6") (pin "C22") (pinfunction "PT116A_C22") (pintype "bidirectional"))
    )
    (net (code "26") (name "/MLVDS_RxTx1_11") (class "Default")
      (node (ref "IC6") (pin "C17") (pinfunction "PT96B_C17") (pintype "bidirectional"))
    )
    (net (code "27") (name "/MLVDS_RxTx1_12") (class "Default")
      (node (ref "IC6") (pin "B23") (pinfunction "PT119B_B23") (pintype "bidirectional"))
    )
    (net (code "28") (name "/MLVDS_RxTx1_13") (class "Default")
      (node (ref "IC6") (pin "C21") (pinfunction "PT112B_C21") (pintype "bidirectional"))
    )
    (net (code "29") (name "/MLVDS_RxTx1_14") (class "Default")
      (node (ref "IC6") (pin "C19") (pinfunction "PT105A_C19") (pintype "bidirectional"))
    )
    (net (code "30") (name "/MLVDS_RxTx1_15") (class "Default")
      (node (ref "IC6") (pin "C18") (pinfunction "PT101A_C18") (pintype "bidirectional"))
    )
    (net (code "32") (name "/MLVDS_RxTx2_8") (class "Default")
      (node (ref "IC6") (pin "A22") (pinfunction "PT110B_A22") (pintype "bidirectional"))
    )
    (net (code "33") (name "/MLVDS_RxTx2_9") (class "Default")
      (node (ref "IC6") (pin "A21") (pinfunction "PT110A_A21") (pintype "bidirectional"))
    )
    (net (code "34") (name "/MLVDS_RxTx2_10") (class "Default")
      (node (ref "IC6") (pin "D19") (pinfunction "PT103B_D19") (pintype "bidirectional"))
    )
    (net (code "35") (name "/MLVDS_RxTx2_11") (class "Default")
      (node (ref "IC6") (pin "B21") (pinfunction "PT112A_B21") (pintype "bidirectional"))
    )
    (net (code "36") (name "/MLVDS_RxTx2_12") (class "Default")
      (node (ref "IC6") (pin "C16") (pinfunction "PT83B_C16") (pintype "bidirectional"))
    )
    (net (code "37") (name "/MLVDS_RxTx2_13") (class "Default")
      (node (ref "IC6") (pin "A15") (pinfunction "PT78B_A15") (pintype "bidirectional"))
    )
    (net (code "38") (name "/MLVDS_RxTx2_14") (class "Default")
      (node (ref "IC6") (pin "A14") (pinfunction "PT78A_A14") (pintype "bidirectional"))
    )
    (net (code "39") (name "/MLVDS_RxTx2_15") (class "Default")
      (node (ref "IC6") (pin "B14") (pinfunction "PT76B_B14") (pintype "bidirectional"))
    )
    (net (code "41") (name "/MLVDS_RxTx3_8") (class "Default")
      (node (ref "IC6") (pin "D17") (pinfunction "PT98A_D17") (pintype "bidirectional"))
    )
    (net (code "42") (name "/MLVDS_RxTx3_9") (class "Default")
      (node (ref "IC6") (pin "A19") (pinfunction "PT107B_A19") (pintype "bidirectional"))
    )
    (net (code "43") (name "/MLVDS_RxTx3_10") (class "Default")
      (node (ref "IC6") (pin "A18") (pinfunction "PT107A_A18") (pintype "bidirectional"))
    )
    (net (code "44") (name "/MLVDS_RxTx3_11") (class "Default")
      (node (ref "IC6") (pin "B17") (pinfunction "PT96A_B17") (pintype "bidirectional"))
    )
    (net (code "45") (name "/MLVDS_RxTx3_12") (class "Default")
      (node (ref "IC6") (pin "D10") (pinfunction "PT54B_D10") (pintype "bidirectional"))
    )
    (net (code "46") (name "/MLVDS_RxTx3_13") (class "Default")
      (node (ref "IC6") (pin "C11") (pinfunction "PT60A/GR_PCLK0_1_C11") (pintype "bidirectional"))
    )
    (net (code "47") (name "/MLVDS_RxTx3_14") (class "Default")
      (node (ref "IC6") (pin "B6") (pinfunction "PT13B_B6") (pintype "bidirectional"))
    )
    (net (code "48") (name "/MLVDS_RxTx3_15") (class "Default")
      (node (ref "IC6") (pin "C9") (pinfunction "PT51B_C9") (pintype "bidirectional"))
    )
    (net (code "50") (name "/MLVDS_RxTx4_8") (class "Default")
      (node (ref "IC6") (pin "A17") (pinfunction "PT85B_A17") (pintype "bidirectional"))
    )
    (net (code "51") (name "/MLVDS_RxTx4_9") (class "Default")
      (node (ref "IC6") (pin "B16") (pinfunction "PT83A_B16") (pintype "bidirectional"))
    )
    (net (code "52") (name "/MLVDS_RxTx4_10") (class "Default")
      (node (ref "IC6") (pin "A16") (pinfunction "PT85A_A16") (pintype "bidirectional"))
    )
    (net (code "53") (name "/MLVDS_RxTx4_11") (class "Default")
      (node (ref "IC6") (pin "C14") (pinfunction "PT74B/GR_PCLK1_1_C14") (pintype "bidirectional"))
    )
    (net (code "54") (name "/MLVDS_RxTx4_12") (class "Default")
      (node (ref "IC6") (pin "C8") (pinfunction "PT20B_C8") (pintype "bidirectional"))
    )
    (net (code "55") (name "/MLVDS_RxTx4_13") (class "Default")
      (node (ref "IC6") (pin "A5") (pinfunction "PT15A_A5") (pintype "bidirectional"))
    )
    (net (code "56") (name "/MLVDS_RxTx4_14") (class "Default")
      (node (ref "IC6") (pin "C5") (pinfunction "PT9B_C5") (pintype "bidirectional"))
    )
    (net (code "57") (name "/MLVDS_RxTx4_15") (class "Default")
      (node (ref "IC6") (pin "D6") (pinfunction "PT11B_D6") (pintype "bidirectional"))
    )
    (net (code "59") (name "/MLVDS_RxTx5_8") (class "Default")
      (node (ref "IC6") (pin "A13") (pinfunction "PT65B/PCLKC0_0_A13") (pintype "bidirectional"))
    )
    (net (code "60") (name "/MLVDS_RxTx5_9") (class "Default")
      (node (ref "IC6") (pin "D14") (pinfunction "PT71B/PCLKC1_0_D14") (pintype "bidirectional"))
    )
    (net (code "61") (name "/MLVDS_RxTx5_10") (class "Default")
      (node (ref "IC6") (pin "A11") (pinfunction "PT58B_A11") (pintype "bidirectional"))
    )
    (net (code "62") (name "/MLVDS_RxTx5_11") (class "Default")
      (node (ref "IC6") (pin "B10") (pinfunction "PT56B_B10") (pintype "bidirectional"))
    )
    (net (code "63") (name "/MLVDS_RxTx5_12") (class "Default")
      (node (ref "IC6") (pin "E6") (pinfunction "PT11A_E6") (pintype "bidirectional"))
    )
    (net (code "64") (name "/MLVDS_RxTx5_13") (class "Default")
      (node (ref "IC6") (pin "D5") (pinfunction "PT9A_D5") (pintype "bidirectional"))
    )
    (net (code "65") (name "/MLVDS_RxTx5_14") (class "Default")
      (node (ref "IC6") (pin "B13") (pinfunction "PT76A_B13") (pintype "bidirectional"))
    )
    (net (code "66") (name "/MLVDS_RxTx5_15") (class "Default")
      (node (ref "IC6") (pin "A10") (pinfunction "PT58A_A10") (pintype "bidirectional"))
    )
    (net (code "68") (name "/MLVDS_RxTx6_8") (class "Default")
      (node (ref "IC6") (pin "C10") (pinfunction "PT56A_C10") (pintype "bidirectional"))
    )
    (net (code "69") (name "/MLVDS_RxTx6_9") (class "Default")
      (node (ref "IC6") (pin "A9") (pinfunction "PT18B_A9") (pintype "bidirectional"))
    )
    (net (code "70") (name "/MLVDS_RxTx6_10") (class "Default")
      (node (ref "IC6") (pin "A8") (pinfunction "PT18A_A8") (pintype "bidirectional"))
    )
    (net (code "71") (name "/MLVDS_RxTx6_11") (class "Default")
      (node (ref "IC6") (pin "C6") (pinfunction "PT13A_C6") (pintype "bidirectional"))
    )
    (net (code "72") (name "/MLVDS_RxTx6_12") (class "Default")
      (node (ref "IC6") (pin "B8") (pinfunction "PT20A_B8") (pintype "bidirectional"))
    )
    (net (code "73") (name "/MLVDS_RxTx6_13") (class "Default")
      (node (ref "IC6") (pin "A6") (pinfunction "PT15B_A6") (pintype "bidirectional"))
    )
    (net (code "74") (name "/MLVDS_RxTx6_14") (class "Default")
      (node (ref "IC6") (pin "A4") (pinfunction "PT6B_A4") (pintype "bidirectional"))
    )
    (net (code "75") (name "/MLVDS_RxTx6_15") (class "Default")
      (node (ref "IC6") (pin "B4") (pinfunction "PT6A_B4") (pintype "bidirectional"))
    )
    (net (code "77") (name "/MOSI") (class "Default")
      (node (ref "D14") (pin "4") (pinfunction "I/O3_4") (pintype "bidirectional"))
      (node (ref "IC6") (pin "AB3") (pinfunction "PB15B/DOUT/CSON_AB3") (pintype "bidirectional"))
    )
    (net (code "78") (name "/PROGRAM_N") (class "Default")
      (node (ref "IC6") (pin "AB4") (pinfunction "PROGRAMN_AB4") (pintype "bidirectional"))
    )
    (net (code "79") (name "/QSPI_CFG_CEN") (class "Default")
      (node (ref "IC6") (pin "AA2") (pinfunction "PB15A/HOLDN/DI/BUSY/CSSPIN/CEN_AA2") (pintype "bidirectional"))
    )
    (net (code "80") (name "/QSPI_CFG_IO2") (class "Default")
      (node (ref "IC6") (pin "AF2") (pinfunction "PB9B/D2/IO2_AF2") (pintype "bidirectional"))
    )
    (net (code "81") (name "/QSPI_CFG_IO3") (class "Default")
      (node (ref "IC6") (pin "AE1") (pinfunction "PB9A/D3/IO3_AE1") (pintype "bidirectional"))
    )
    (net (code "82") (name "/QSPI_CFG_MISO_IO1") (class "Default")
      (node (ref "IC6") (pin "AD2") (pinfunction "PB11A/D1/MISO/IO1_AD2") (pintype "bidirectional"))
    )
    (net (code "83") (name "/QSPI_CFG_MOSI_IO0") (class "Default")
      (node (ref "IC6") (pin "AE2") (pinfunction "PB11B/D0/MOSI/IO0_AE2") (pintype "bidirectional"))
    )
    (net (code "84") (name "/QSPI_CFG_SCK") (class "Default")
      (node (ref "IC6") (pin "AE3") (pinfunction "CCLK/MCLK/SCK_AE3") (pintype "bidirectional"))
    )
    (net (code "85") (name "/QSPI_CLK") (class "Default")
      (node (ref "IC6") (pin "E11") (pinfunction "PT63A/PCLKT0_1_E11") (pintype "bidirectional"))
    )
    (net (code "86") (name "/QSPI_IO0") (class "Default")
      (node (ref "IC6") (pin "AB24") (pinfunction "PB110A_AB24") (pintype "bidirectional"))
    )
    (net (code "87") (name "/QSPI_IO1") (class "Default")
      (node (ref "IC6") (pin "AA24") (pinfunction "PB110B_AA24") (pintype "bidirectional"))
    )
    (net (code "88") (name "/QSPI_IO2") (class "Default")
      (node (ref "IC6") (pin "AA23") (pinfunction "PB107B_AA23") (pintype "bidirectional"))
    )
    (net (code "89") (name "/QSPI_IO3") (class "Default")
      (node (ref "IC6") (pin "AA22") (pinfunction "PB107A_AA22") (pintype "bidirectional"))
    )
    (net (code "90") (name "/QSPI_NCS") (class "Default")
      (node (ref "IC6") (pin "AF25") (pinfunction "PB116A_AF25") (pintype "bidirectional"))
    )
    (net (code "91") (name "/SCK") (class "Default")
      (node (ref "D13") (pin "4") (pinfunction "I/O3_4") (pintype "bidirectional"))
      (node (ref "IC6") (pin "A25") (pinfunction "PT121B/URC_GPLL1C_IN_A25") (pintype "bidirectional"))
    )
    (net (code "92") (name "/SLOT1.LVDS_0_N") (class "Default")
      (node (ref "R101") (pin "2") (pinfunction "2_2") (pintype "passive"))
      (node (ref "R91") (pin "1") (pinfunction "1_1") (pintype "passive"))
    )
    (net (code "93") (name "/SLOT1.LVDS_0_P") (class "Default")
      (node (ref "R90") (pin "2") (pinfunction "2_2") (pintype "passive"))
      (node (ref "R91") (pin "2") (pinfunction "2_2") (pintype "passive"))
    )
    (net (code "94") (name "/SLOT1.LVDS_1_N") (class "Default")
      (node (ref "R122") (pin "1") (pinfunction "1_1") (pintype "passive"))
      (node (ref "R129") (pin "2") (pinfunction "2_2") (pintype "passive"))
    )
    (net (code "95") (name "/SLOT1.LVDS_1_P") (class "Default")
      (node (ref "R121") (pin "2") (pinfunction "2_2") (pintype "passive"))
      (node (ref "R122") (pin "2") (pinfunction "2_2") (pintype "passive"))
    )
    (net (code "96") (name "/SLOT1.LVDS_2_N") (class "Default")
      (node (ref "IC6") (pin "V21") (pinfunction "PR80B_V21") (pintype "bidirectional"))
    )
    (net (code "97") (name "/SLOT1.LVDS_2_P") (class "Default")
      (node (ref "IC6") (pin "W23") (pinfunction "PR80A_W23") (pintype "bidirectional"))
    )
    (net (code "98") (name "/SLOT1.LVDS_3_N") (class "Default")
      (node (ref "R85") (pin "1") (pinfunction "1_1") (pintype "passive"))
      (node (ref "R88") (pin "2") (pinfunction "2_2") (pintype "passive"))
    )
    (net (code "99") (name "/SLOT1.LVDS_3_P") (class "Default")
      (node (ref "R84") (pin "2") (pinfunction "2_2") (pintype "passive"))
      (node (ref "R85") (pin "2") (pinfunction "2_2") (pintype "passive"))
    )
    (net (code "100") (name "/SLOT1.LVDS_4_N") (class "Default")
      (node (ref "IC6") (pin "W26") (pinfunction "PR92B_W26") (pintype "bidirectional"))
    )
    (net (code "101") (name "/SLOT1.LVDS_4_P") (class "Default")
      (node (ref "IC6") (pin "V24") (pinfunction "PR92A_V24") (pintype "bidirectional"))
    )
    (net (code "102") (name "/SLOT1.LVDS_5_N") (class "Default")
      (node (ref "IC6") (pin "U25") (pinfunction "PR89B_U25") (pintype "bidirectional"))
    )
    (net (code "103") (name "/SLOT1.LVDS_5_P") (class "Default")
      (node (ref "IC6") (pin "V26") (pinfunction "PR89A_V26") (pintype "bidirectional"))
    )
    (net (code "104") (name "/SLOT1.LVDS_6_N") (class "Default")
      (node (ref "IC6") (pin "U22") (pinfunction "PR77B_U22") (pintype "bidirectional"))
    )
    (net (code "105") (name "/SLOT1.LVDS_6_P") (class "Default")
      (node (ref "IC6") (pin "V23") (pinfunction "PR77A_V23") (pintype "bidirectional"))
    )
    (net (code "106") (name "/SLOT1.LVDS_7_N") (class "Default")
      (node (ref "IC6") (pin "U24") (pinfunction "PR83B_U24") (pintype "bidirectional"))
    )
    (net (code "107") (name "/SLOT1.LVDS_7_P") (class "Default")
      (node (ref "IC6") (pin "T24") (pinfunction "PR83A_T24") (pintype "bidirectional"))
    )
    (net (code "108") (name "/SLOT1.LVDSr0_N") (class "Default")
      (node (ref "IC6") (pin "W21") (pinfunction "PR80D_W21") (pintype "bidirectional"))
      (node (ref "R101") (pin "1") (pinfunction "1_1") (pintype "passive"))
    )
    (net (code "109") (name "/SLOT1.LVDSr0_P") (class "Default")
      (node (ref "IC6") (pin "W22") (pinfunction "PR80C_W22") (pintype "bidirectional"))
      (node (ref "R90") (pin "1") (pinfunction "1_1") (pintype "passive"))
    )
    (net (code "110") (name "/SLOT1.LVDSr1_N") (class "Default")
      (node (ref "IC6") (pin "W24") (pinfunction "PR92D/LRC_GPLL0C_IN_W24") (pintype "bidirectional"))
      (node (ref "R129") (pin "1") (pinfunction "1_1") (pintype "passive"))
    )
    (net (code "111") (name "/SLOT1.LVDSr1_P") (class "Default")
      (node (ref "IC6") (pin "W25") (pinfunction "PR92C/LRC_GPLL0T_IN_W25") (pintype "bidirectional"))
      (node (ref "R121") (pin "1") (pinfunction "1_1") (pintype "passive"))
    )
    (net (code "112") (name "/SLOT1.LVDSr3_N") (class "Default")
      (node (ref "IC6") (pin "U23") (pinfunction "PR77D_U23") (pintype "bidirectional"))
      (node (ref "R88") (pin "1") (pinfunction "1_1") (pintype "passive"))
    )
    (net (code "113") (name "/SLOT1.LVDSr3_P") (class "Default")
      (node (ref "IC6") (pin "U21") (pinfunction "PR77C_U21") (pintype "bidirectional"))
      (node (ref "R84") (pin "1") (pinfunction "1_1") (pintype "passive"))
    )
    (net (code "114") (name "/SLOT2.LVDS_0_N") (class "Default")
      (node (ref "R79") (pin "1") (pinfunction "1_1") (pintype "passive"))
      (node (ref "R82") (pin "2") (pinfunction "2_2") (pintype "passive"))
    )
    (net (code "115") (name "/SLOT2.LVDS_0_P") (class "Default")
      (node (ref "R74") (pin "2") (pinfunction "2_2") (pintype "passive"))
      (node (ref "R79") (pin "2") (pinfunction "2_2") (pintype "passive"))
    )
    (net (code "116") (name "/SLOT2.LVDS_1_N") (class "Default")
      (node (ref "R52") (pin "1") (pinfunction "1_1") (pintype "passive"))
      (node (ref "R56") (pin "2") (pinfunction "2_2") (pintype "passive"))
    )
    (net (code "117") (name "/SLOT2.LVDS_1_P") (class "Default")
      (node (ref "R51") (pin "2") (pinfunction "2_2") (pintype "passive"))
      (node (ref "R52") (pin "2") (pinfunction "2_2") (pintype "passive"))
    )
    (net (code "118") (name "/SLOT2.LVDS_2_N") (class "Default")
      (node (ref "IC6") (pin "L23") (pinfunction "PR44B/PCLKC2_1_L23") (pintype "bidirectional"))
    )
    (net (code "119") (name "/SLOT2.LVDS_2_P") (class "Default")
      (node (ref "IC6") (pin "K23") (pinfunction "PR44A/PCLKT2_1_K23") (pintype "bidirectional"))
    )
    (net (code "120") (name "/SLOT2.LVDS_3_N") (class "Default")
      (node (ref "R248") (pin "1") (pinfunction "1_1") (pintype "passive"))
      (node (ref "R249") (pin "2") (pinfunction "2_2") (pintype "passive"))
    )
    (net (code "121") (name "/SLOT2.LVDS_3_P") (class "Default")
      (node (ref "R247") (pin "2") (pinfunction "2_2") (pintype "passive"))
      (node (ref "R248") (pin "2") (pinfunction "2_2") (pintype "passive"))
    )
    (net (code "122") (name "/SLOT2.LVDS_4_N") (class "Default")
      (node (ref "IC6") (pin "D24") (pinfunction "PR14B_D24") (pintype "bidirectional"))
    )
    (net (code "123") (name "/SLOT2.LVDS_4_P") (class "Default")
      (node (ref "IC6") (pin "D23") (pinfunction "PR14A_D23") (pintype "bidirectional"))
    )
    (net (code "124") (name "/SLOT2.LVDS_5_N") (class "Default")
      (node (ref "IC6") (pin "P22") (pinfunction "PR71B_P22") (pintype "bidirectional"))
    )
    (net (code "125") (name "/SLOT2.LVDS_5_P") (class "Default")
      (node (ref "IC6") (pin "P23") (pinfunction "PR71A_P23") (pintype "bidirectional"))
    )
    (net (code "126") (name "/SLOT2.LVDS_6_N") (class "Default")
      (node (ref "IC6") (pin "T22") (pinfunction "PR74B_T22") (pintype "bidirectional"))
    )
    (net (code "127") (name "/SLOT2.LVDS_6_P") (class "Default")
      (node (ref "IC6") (pin "R23") (pinfunction "PR74A_R23") (pintype "bidirectional"))
    )
    (net (code "128") (name "/SLOT2.LVDS_7_N") (class "Default")
      (node (ref "IC6") (pin "P26") (pinfunction "PR86B_P26") (pintype "bidirectional"))
    )
    (net (code "129") (name "/SLOT2.LVDS_7_P") (class "Default")
      (node (ref "IC6") (pin "P25") (pinfunction "PR86A_P25") (pintype "bidirectional"))
    )
    (net (code "130") (name "/SLOT2.LVDSr0_N") (class "Default")
      (node (ref "IC6") (pin "T23") (pinfunction "PR74D_T23") (pintype "bidirectional"))
      (node (ref "R82") (pin "1") (pinfunction "1_1") (pintype "passive"))
    )
    (net (code "131") (name "/SLOT2.LVDSr0_P") (class "Default")
      (node (ref "IC6") (pin "R21") (pinfunction "PR74C_R21") (pintype "bidirectional"))
      (node (ref "R74") (pin "1") (pinfunction "1_1") (pintype "passive"))
    )
    (net (code "132") (name "/SLOT2.LVDSr1_N") (class "Default")
      (node (ref "IC6") (pin "L26") (pinfunction "PR53D_L26") (pintype "bidirectional"))
      (node (ref "R56") (pin "1") (pinfunction "1_1") (pintype "passive"))
    )
    (net (code "133") (name "/SLOT2.LVDSr1_P") (class "Default")
      (node (ref "IC6") (pin "K26") (pinfunction "PR53C_K26") (pintype "bidirectional"))
      (node (ref "R51") (pin "1") (pinfunction "1_1") (pintype "passive"))
    )
    (net (code "134") (name "/SLOT2.LVDSr3_N") (class "Default")
      (node (ref "IC6") (pin "C24") (pinfunction "PR11D_C24") (pintype "bidirectional"))
      (node (ref "R249") (pin "1") (pinfunction "1_1") (pintype "passive"))
    )
    (net (code "135") (name "/SLOT2.LVDSr3_P") (class "Default")
      (node (ref "IC6") (pin "C23") (pinfunction "PR11C_C23") (pintype "bidirectional"))
      (node (ref "R247") (pin "1") (pinfunction "1_1") (pintype "passive"))
    )
    (net (code "136") (name "/SLOT3.LVDS_0_N") (class "Default")
      (node (ref "R104") (pin "1") (pinfunction "1_1") (pintype "passive"))
      (node (ref "R107") (pin "2") (pinfunction "2_2") (pintype "passive"))
    )
    (net (code "137") (name "/SLOT3.LVDS_0_P") (class "Default")
      (node (ref "R103") (pin "2") (pinfunction "2_2") (pintype "passive"))
      (node (ref "R104") (pin "2") (pinfunction "2_2") (pintype "passive"))
    )
    (net (code "138") (name "/SLOT3.LVDS_1_N") (class "Default")
      (node (ref "R23") (pin "1") (pinfunction "1_1") (pintype "passive"))
      (node (ref "R26") (pin "2") (pinfunction "2_2") (pintype "passive"))
    )
    (net (code "139") (name "/SLOT3.LVDS_1_P") (class "Default")
      (node (ref "R22") (pin "2") (pinfunction "2_2") (pintype "passive"))
      (node (ref "R23") (pin "2") (pinfunction "2_2") (pintype "passive"))
    )
    (net (code "140") (name "/SLOT3.LVDS_2_N") (class "Default")
      (node (ref "IC6") (pin "J23") (pinfunction "PR41B_J23") (pintype "bidirectional"))
    )
    (net (code "141") (name "/SLOT3.LVDS_2_P") (class "Default")
      (node (ref "IC6") (pin "K22") (pinfunction "PR41A/GR_PCLK2_1_K22") (pintype "bidirectional"))
    )
    (net (code "142") (name "/SLOT3.LVDS_3_N") (class "Default")
      (node (ref "R134") (pin "1") (pinfunction "1_1") (pintype "passive"))
      (node (ref "R144") (pin "2") (pinfunction "2_2") (pintype "passive"))
    )
    (net (code "143") (name "/SLOT3.LVDS_3_P") (class "Default")
      (node (ref "R133") (pin "2") (pinfunction "2_2") (pintype "passive"))
      (node (ref "R134") (pin "2") (pinfunction "2_2") (pintype "passive"))
    )
    (net (code "144") (name "/SLOT3.LVDS_4_N") (class "Default")
      (node (ref "IC6") (pin "F26") (pinfunction "PR20B_F26") (pintype "bidirectional"))
    )
    (net (code "145") (name "/SLOT3.LVDS_4_P") (class "Default")
      (node (ref "IC6") (pin "F25") (pinfunction "PR20A_F25") (pintype "bidirectional"))
    )
    (net (code "146") (name "/SLOT3.LVDS_5_N") (class "Default")
      (node (ref "IC6") (pin "K6") (pinfunction "PL38B_K6") (pintype "bidirectional"))
    )
    (net (code "147") (name "/SLOT3.LVDS_5_P") (class "Default")
      (node (ref "IC6") (pin "J6") (pinfunction "PL38A_J6") (pintype "bidirectional"))
    )
    (net (code "148") (name "/SLOT3.LVDS_6_N") (class "Default")
      (node (ref "IC6") (pin "C1") (pinfunction "PL11B/ULC_GPLL0C_IN_C1") (pintype "bidirectional"))
    )
    (net (code "149") (name "/SLOT3.LVDS_6_P") (class "Default")
      (node (ref "IC6") (pin "C2") (pinfunction "PL11A/ULC_GPLL0T_IN_C2") (pintype "bidirectional"))
    )
    (net (code "150") (name "/SLOT3.LVDS_7_N") (class "Default")
      (node (ref "IC6") (pin "J4") (pinfunction "PL41B_J4") (pintype "bidirectional"))
    )
    (net (code "151") (name "/SLOT3.LVDS_7_P") (class "Default")
      (node (ref "IC6") (pin "K5") (pinfunction "PL41A/GR_PCLK7_1_K5") (pintype "bidirectional"))
    )
    (net (code "152") (name "/SLOT3.LVDSr0_N") (class "Default")
      (node (ref "IC6") (pin "P24") (pinfunction "PR83D_P24") (pintype "bidirectional"))
      (node (ref "R107") (pin "1") (pinfunction "1_1") (pintype "passive"))
    )
    (net (code "153") (name "/SLOT3.LVDSr0_P") (class "Default")
      (node (ref "IC6") (pin "R24") (pinfunction "PR83C_R24") (pintype "bidirectional"))
      (node (ref "R103") (pin "1") (pinfunction "1_1") (pintype "passive"))
    )
    (net (code "154") (name "/SLOT3.LVDSr1_N") (class "Default")
      (node (ref "IC6") (pin "H26") (pinfunction "PR47D/PCLKC3_0_H26") (pintype "bidirectional"))
      (node (ref "R26") (pin "1") (pinfunction "1_1") (pintype "passive"))
    )
    (net (code "155") (name "/SLOT3.LVDSr1_P") (class "Default")
      (node (ref "IC6") (pin "H25") (pinfunction "PR47C/PCLKT3_0_H25") (pintype "bidirectional"))
      (node (ref "R22") (pin "1") (pinfunction "1_1") (pintype "passive"))
    )
    (net (code "156") (name "/SLOT3.LVDSr3_N") (class "Default")
      (node (ref "IC6") (pin "H6") (pinfunction "PL35D_H6") (pintype "bidirectional"))
      (node (ref "R144") (pin "1") (pinfunction "1_1") (pintype "passive"))
    )
    (net (code "157") (name "/SLOT3.LVDSr3_P") (class "Default")
      (node (ref "IC6") (pin "H5") (pinfunction "PL35C/VREF1_7_H5") (pintype "bidirectional"))
      (node (ref "R133") (pin "1") (pinfunction "1_1") (pintype "passive"))
    )
    (net (code "158") (name "/SLOT4.LVDS_0_N") (class "Default")
      (node (ref "R68") (pin "1") (pinfunction "1_1") (pintype "passive"))
      (node (ref "R71") (pin "2") (pinfunction "2_2") (pintype "passive"))
    )
    (net (code "159") (name "/SLOT4.LVDS_0_P") (class "Default")
      (node (ref "R67") (pin "2") (pinfunction "2_2") (pintype "passive"))
      (node (ref "R68") (pin "2") (pinfunction "2_2") (pintype "passive"))
    )
    (net (code "160") (name "/SLOT4.LVDS_1_N") (class "Default")
      (node (ref "R254") (pin "1") (pinfunction "1_1") (pintype "passive"))
      (node (ref "R255") (pin "2") (pinfunction "2_2") (pintype "passive"))
    )
    (net (code "161") (name "/SLOT4.LVDS_1_P") (class "Default")
      (node (ref "R253") (pin "2") (pinfunction "2_2") (pintype "passive"))
      (node (ref "R254") (pin "2") (pinfunction "2_2") (pintype "passive"))
    )
    (net (code "162") (name "/SLOT4.LVDS_2_N") (class "Default")
      (node (ref "IC6") (pin "J24") (pinfunction "PR47B/PCLKC3_1_J24") (pintype "bidirectional"))
    )
    (net (code "163") (name "/SLOT4.LVDS_2_P") (class "Default")
      (node (ref "IC6") (pin "H24") (pinfunction "PR47A/PCLKT3_1_H24") (pintype "bidirectional"))
    )
    (net (code "164") (name "/SLOT4.LVDS_3_N") (class "Default")
      (node (ref "R149") (pin "1") (pinfunction "1_1") (pintype "passive"))
      (node (ref "R150") (pin "2") (pinfunction "2_2") (pintype "passive"))
    )
    (net (code "165") (name "/SLOT4.LVDS_3_P") (class "Default")
      (node (ref "R148") (pin "2") (pinfunction "2_2") (pintype "passive"))
      (node (ref "R149") (pin "2") (pinfunction "2_2") (pintype "passive"))
    )
    (net (code "166") (name "/SLOT4.LVDS_4_N") (class "Default")
      (node (ref "IC6") (pin "F23") (pinfunction "PR35B_F23") (pintype "bidirectional"))
    )
    (net (code "167") (name "/SLOT4.LVDS_4_P") (class "Default")
      (node (ref "IC6") (pin "F22") (pinfunction "PR35A_F22") (pintype "bidirectional"))
    )
    (net (code "168") (name "/SLOT4.LVDS_5_N") (class "Default")
      (node (ref "IC6") (pin "L4") (pinfunction "PL44B/PCLKC7_1_L4") (pintype "bidirectional"))
    )
    (net (code "169") (name "/SLOT4.LVDS_5_P") (class "Default")
      (node (ref "IC6") (pin "K4") (pinfunction "PL44A/PCLKT7_1_K4") (pintype "bidirectional"))
    )
    (net (code "170") (name "/SLOT4.LVDS_6_N") (class "Default")
      (node (ref "IC6") (pin "E1") (pinfunction "PL17B_E1") (pintype "bidirectional"))
    )
    (net (code "171") (name "/SLOT4.LVDS_6_P") (class "Default")
      (node (ref "IC6") (pin "D2") (pinfunction "PL17A_D2") (pintype "bidirectional"))
    )
    (net (code "172") (name "/SLOT4.LVDS_7_N") (class "Default")
      (node (ref "IC6") (pin "F1") (pinfunction "PL20B_F1") (pintype "bidirectional"))
    )
    (net (code "173") (name "/SLOT4.LVDS_7_P") (class "Default")
      (node (ref "IC6") (pin "F2") (pinfunction "PL20A_F2") (pintype "bidirectional"))
    )
    (net (code "174") (name "/SLOT4.LVDSr0_N") (class "Default")
      (node (ref "IC6") (pin "N23") (pinfunction "PR71D_N23") (pintype "bidirectional"))
      (node (ref "R71") (pin "1") (pinfunction "1_1") (pintype "passive"))
    )
    (net (code "175") (name "/SLOT4.LVDSr0_P") (class "Default")
      (node (ref "IC6") (pin "P21") (pinfunction "PR71C_P21") (pintype "bidirectional"))
      (node (ref "R67") (pin "1") (pinfunction "1_1") (pintype "passive"))
    )
    (net (code "176") (name "/SLOT4.LVDSr1_N") (class "Default")
      (node (ref "IC6") (pin "D26") (pinfunction "PR17D_D26") (pintype "bidirectional"))
      (node (ref "R255") (pin "1") (pinfunction "1_1") (pintype "passive"))
    )
    (net (code "177") (name "/SLOT4.LVDSr1_P") (class "Default")
      (node (ref "IC6") (pin "E24") (pinfunction "PR17C_E24") (pintype "bidirectional"))
      (node (ref "R253") (pin "1") (pinfunction "1_1") (pintype "passive"))
    )
    (net (code "178") (name "/SLOT4.LVDSr3_N") (class "Default")
      (node (ref "IC6") (pin "F3") (pinfunction "PL20D_F3") (pintype "bidirectional"))
      (node (ref "R150") (pin "1") (pinfunction "1_1") (pintype "passive"))
    )
    (net (code "179") (name "/SLOT4.LVDSr3_P") (class "Default")
      (node (ref "IC6") (pin "E4") (pinfunction "PL20C_E4") (pintype "bidirectional"))
      (node (ref "R148") (pin "1") (pinfunction "1_1") (pintype "passive"))
    )
    (net (code "180") (name "/SLOT5.LVDS_0_N") (class "Default")
      (node (ref "R260") (pin "1") (pinfunction "1_1") (pintype "passive"))
      (node (ref "R261") (pin "2") (pinfunction "2_2") (pintype "passive"))
    )
    (net (code "181") (name "/SLOT5.LVDS_0_P") (class "Default")
      (node (ref "R259") (pin "2") (pinfunction "2_2") (pintype "passive"))
      (node (ref "R260") (pin "2") (pinfunction "2_2") (pintype "passive"))
    )
    (net (code "182") (name "/SLOT5.LVDS_1_N") (class "Default")
      (node (ref "R277") (pin "1") (pinfunction "1_1") (pintype "passive"))
      (node (ref "R278") (pin "2") (pinfunction "2_2") (pintype "passive"))
    )
    (net (code "183") (name "/SLOT5.LVDS_1_P") (class "Default")
      (node (ref "R276") (pin "2") (pinfunction "2_2") (pintype "passive"))
      (node (ref "R277") (pin "2") (pinfunction "2_2") (pintype "passive"))
    )
    (net (code "184") (name "/SLOT5.LVDS_2_N") (class "Default")
      (node (ref "IC6") (pin "N25") (pinfunction "PR56B/VREF1_3_N25") (pintype "bidirectional"))
    )
    (net (code "185") (name "/SLOT5.LVDS_2_P") (class "Default")
      (node (ref "IC6") (pin "N26") (pinfunction "PR56A_N26") (pintype "bidirectional"))
    )
    (net (code "186") (name "/SLOT5.LVDS_3_N") (class "Default")
      (node (ref "R152") (pin "1") (pinfunction "1_1") (pintype "passive"))
      (node (ref "R153") (pin "2") (pinfunction "2_2") (pintype "passive"))
    )
    (net (code "187") (name "/SLOT5.LVDS_3_P") (class "Default")
      (node (ref "R151") (pin "2") (pinfunction "2_2") (pintype "passive"))
      (node (ref "R152") (pin "2") (pinfunction "2_2") (pintype "passive"))
    )
    (net (code "188") (name "/SLOT5.LVDS_4_N") (class "Default")
      (node (ref "IC6") (pin "E26") (pinfunction "PR17B_E26") (pintype "bidirectional"))
    )
    (net (code "189") (name "/SLOT5.LVDS_4_P") (class "Default")
      (node (ref "IC6") (pin "D25") (pinfunction "PR17A_D25") (pintype "bidirectional"))
    )
    (net (code "190") (name "/SLOT5.LVDS_5_N") (class "Default")
      (node (ref "IC6") (pin "J3") (pinfunction "PL47B/PCLKC6_1_J3") (pintype "bidirectional"))
    )
    (net (code "191") (name "/SLOT5.LVDS_5_P") (class "Default")
      (node (ref "IC6") (pin "H3") (pinfunction "PL47A/PCLKT6_1_H3") (pintype "bidirectional"))
    )
    (net (code "192") (name "/SLOT5.LVDS_6_N") (class "Default")
      (node (ref "IC6") (pin "P5") (pinfunction "PL71B_P5") (pintype "bidirectional"))
    )
    (net (code "193") (name "/SLOT5.LVDS_6_P") (class "Default")
      (node (ref "IC6") (pin "P4") (pinfunction "PL71A_P4") (pintype "bidirectional"))
    )
    (net (code "194") (name "/SLOT5.LVDS_7_N") (class "Default")
      (node (ref "IC6") (pin "T5") (pinfunction "PL74B_T5") (pintype "bidirectional"))
    )
    (net (code "195") (name "/SLOT5.LVDS_7_P") (class "Default")
      (node (ref "IC6") (pin "R4") (pinfunction "PL74A_R4") (pintype "bidirectional"))
    )
    (net (code "196") (name "/SLOT5.LVDSr0_N") (class "Default")
      (node (ref "IC6") (pin "H21") (pinfunction "PR35D_H21") (pintype "bidirectional"))
      (node (ref "R261") (pin "1") (pinfunction "1_1") (pintype "passive"))
    )
    (net (code "197") (name "/SLOT5.LVDSr0_P") (class "Default")
      (node (ref "IC6") (pin "H22") (pinfunction "PR35C/VREF1_2_H22") (pintype "bidirectional"))
      (node (ref "R259") (pin "1") (pinfunction "1_1") (pintype "passive"))
    )
    (net (code "198") (name "/SLOT5.LVDSr1_N") (class "Default")
      (node (ref "IC6") (pin "M23") (pinfunction "PR41D_M23") (pintype "bidirectional"))
      (node (ref "R278") (pin "1") (pinfunction "1_1") (pintype "passive"))
    )
    (net (code "199") (name "/SLOT5.LVDSr1_P") (class "Default")
      (node (ref "IC6") (pin "M21") (pinfunction "PR41C/GR_PCLK2_0_M21") (pintype "bidirectional"))
      (node (ref "R276") (pin "1") (pinfunction "1_1") (pintype "passive"))
    )
    (net (code "200") (name "/SLOT5.LVDSr3_N") (class "Default")
      (node (ref "IC6") (pin "C3") (pinfunction "PL11D_C3") (pintype "bidirectional"))
      (node (ref "R153") (pin "1") (pinfunction "1_1") (pintype "passive"))
    )
    (net (code "201") (name "/SLOT5.LVDSr3_P") (class "Default")
      (node (ref "IC6") (pin "C4") (pinfunction "PL11C_C4") (pintype "bidirectional"))
      (node (ref "R151") (pin "1") (pinfunction "1_1") (pintype "passive"))
    )
    (net (code "202") (name "/SLOT6.LVDS_0_N") (class "Default")
      (node (ref "R29") (pin "1") (pinfunction "1_1") (pintype "passive"))
      (node (ref "R38") (pin "2") (pinfunction "2_2") (pintype "passive"))
    )
    (net (code "203") (name "/SLOT6.LVDS_0_P") (class "Default")
      (node (ref "R28") (pin "2") (pinfunction "2_2") (pintype "passive"))
      (node (ref "R29") (pin "2") (pinfunction "2_2") (pintype "passive"))
    )
    (net (code "204") (name "/SLOT6.LVDS_1_N") (class "Default")
      (node (ref "R280") (pin "1") (pinfunction "1_1") (pintype "passive"))
      (node (ref "R281") (pin "2") (pinfunction "2_2") (pintype "passive"))
    )
    (net (code "205") (name "/SLOT6.LVDS_1_P") (class "Default")
      (node (ref "R279") (pin "2") (pinfunction "2_2") (pintype "passive"))
      (node (ref "R280") (pin "2") (pinfunction "2_2") (pintype "passive"))
    )
    (net (code "206") (name "/SLOT6.LVDS_2_N") (class "Default")
      (node (ref "IC6") (pin "J26") (pinfunction "PR50B_J26") (pintype "bidirectional"))
    )
    (net (code "207") (name "/SLOT6.LVDS_2_P") (class "Default")
      (node (ref "IC6") (pin "K25") (pinfunction "PR50A/GR_PCLK3_0_K25") (pintype "bidirectional"))
    )
    (net (code "208") (name "/SLOT6.LVDS_3_N") (class "Default")
      (node (ref "R155") (pin "1") (pinfunction "1_1") (pintype "passive"))
      (node (ref "R156") (pin "2") (pinfunction "2_2") (pintype "passive"))
    )
    (net (code "209") (name "/SLOT6.LVDS_3_P") (class "Default")
      (node (ref "R154") (pin "2") (pinfunction "2_2") (pintype "passive"))
      (node (ref "R155") (pin "2") (pinfunction "2_2") (pintype "passive"))
    )
    (net (code "210") (name "/SLOT6.LVDS_4_N") (class "Default")
      (node (ref "IC6") (pin "C26") (pinfunction "PR11B/URC_GPLL0C_IN_C26") (pintype "bidirectional"))
    )
    (net (code "211") (name "/SLOT6.LVDS_4_P") (class "Default")
      (node (ref "IC6") (pin "C25") (pinfunction "PR11A/URC_GPLL0T_IN_C25") (pintype "bidirectional"))
    )
    (net (code "212") (name "/SLOT6.LVDS_5_N") (class "Default")
      (node (ref "IC6") (pin "J1") (pinfunction "PL50B_J1") (pintype "bidirectional"))
    )
    (net (code "213") (name "/SLOT6.LVDS_5_P") (class "Default")
      (node (ref "IC6") (pin "K2") (pinfunction "PL50A/GR_PCLK6_0_K2") (pintype "bidirectional"))
    )
    (net (code "214") (name "/SLOT6.LVDS_6_N") (class "Default")
      (node (ref "IC6") (pin "M1") (pinfunction "PL53B_M1") (pintype "bidirectional"))
    )
    (net (code "215") (name "/SLOT6.LVDS_6_P") (class "Default")
      (node (ref "IC6") (pin "L2") (pinfunction "PL53A_L2") (pintype "bidirectional"))
    )
    (net (code "216") (name "/SLOT6.LVDS_7_N") (class "Default")
      (node (ref "IC6") (pin "U3") (pinfunction "PL83B_U3") (pintype "bidirectional"))
    )
    (net (code "217") (name "/SLOT6.LVDS_7_P") (class "Default")
      (node (ref "IC6") (pin "T3") (pinfunction "PL83A_T3") (pintype "bidirectional"))
    )
    (net (code "218") (name "/SLOT6.LVDSr0_N") (class "Default")
      (node (ref "IC6") (pin "L24") (pinfunction "PR50D_L24") (pintype "bidirectional"))
      (node (ref "R38") (pin "1") (pinfunction "1_1") (pintype "passive"))
    )
    (net (code "219") (name "/SLOT6.LVDSr0_P") (class "Default")
      (node (ref "IC6") (pin "K24") (pinfunction "PR50C/GR_PCLK3_1_K24") (pintype "bidirectional"))
      (node (ref "R28") (pin "1") (pinfunction "1_1") (pintype "passive"))
    )
    (net (code "220") (name "/SLOT6.LVDSr1_N") (class "Default")
      (node (ref "IC6") (pin "N22") (pinfunction "PR44D/PCLKC2_0_N22") (pintype "bidirectional"))
      (node (ref "R281") (pin "1") (pinfunction "1_1") (pintype "passive"))
    )
    (net (code "221") (name "/SLOT6.LVDSr1_P") (class "Default")
      (node (ref "IC6") (pin "N21") (pinfunction "PR44C/PCLKT2_0_N21") (pintype "bidirectional"))
      (node (ref "R279") (pin "1") (pinfunction "1_1") (pintype "passive"))
    )
    (net (code "222") (name "/SLOT6.LVDSr3_N") (class "Default")
      (node (ref "IC6") (pin "D1") (pinfunction "PL17D_D1") (pintype "bidirectional"))
      (node (ref "R156") (pin "1") (pinfunction "1_1") (pintype "passive"))
    )
    (net (code "223") (name "/SLOT6.LVDSr3_P") (class "Default")
      (node (ref "IC6") (pin "E3") (pinfunction "PL17C_E3") (pintype "bidirectional"))
      (node (ref "R154") (pin "1") (pinfunction "1_1") (pintype "passive"))
    )
    (net (code "224") (name "/SLOT7.LVDS_0_N") (class "Default")
      (node (ref "R274") (pin "1") (pinfunction "1_1") (pintype "passive"))
      (node (ref "R275") (pin "2") (pinfunction "2_2") (pintype "passive"))
    )
    (net (code "225") (name "/SLOT7.LVDS_0_P") (class "Default")
      (node (ref "R273") (pin "2") (pinfunction "2_2") (pintype "passive"))
      (node (ref "R274") (pin "2") (pinfunction "2_2") (pintype "passive"))
    )
    (net (code "226") (name "/SLOT7.LVDS_1_N") (class "Default")
      (node (ref "R251") (pin "1") (pinfunction "1_1") (pintype "passive"))
      (node (ref "R252") (pin "2") (pinfunction "2_2") (pintype "passive"))
    )
    (net (code "227") (name "/SLOT7.LVDS_1_P") (class "Default")
      (node (ref "R250") (pin "2") (pinfunction "2_2") (pintype "passive"))
      (node (ref "R251") (pin "2") (pinfunction "2_2") (pintype "passive"))
    )
    (net (code "228") (name "/SLOT7.LVDS_2_N") (class "Default")
      (node (ref "IC6") (pin "K21") (pinfunction "PR38B_K21") (pintype "bidirectional"))
    )
    (net (code "229") (name "/SLOT7.LVDS_2_P") (class "Default")
      (node (ref "IC6") (pin "J21") (pinfunction "PR38A_J21") (pintype "bidirectional"))
    )
    (net (code "230") (name "/SLOT7.LVDS_3_N") (class "Default")
      (node (ref "R158") (pin "1") (pinfunction "1_1") (pintype "passive"))
      (node (ref "R159") (pin "2") (pinfunction "2_2") (pintype "passive"))
    )
    (net (code "231") (name "/SLOT7.LVDS_3_P") (class "Default")
      (node (ref "R157") (pin "2") (pinfunction "2_2") (pintype "passive"))
      (node (ref "R158") (pin "2") (pinfunction "2_2") (pintype "passive"))
    )
    (net (code "232") (name "/SLOT7.LVDS_4_N") (class "Default")
      (node (ref "IC6") (pin "D3") (pinfunction "PL14B_D3") (pintype "bidirectional"))
    )
    (net (code "233") (name "/SLOT7.LVDS_4_P") (class "Default")
      (node (ref "IC6") (pin "D4") (pinfunction "PL14A_D4") (pintype "bidirectional"))
    )
    (net (code "234") (name "/SLOT7.LVDS_5_N") (class "Default")
      (node (ref "IC6") (pin "P1") (pinfunction "PL86B_P1") (pintype "bidirectional"))
    )
    (net (code "235") (name "/SLOT7.LVDS_5_P") (class "Default")
      (node (ref "IC6") (pin "P2") (pinfunction "PL86A_P2") (pintype "bidirectional"))
    )
    (net (code "236") (name "/SLOT7.LVDS_6_N") (class "Default")
      (node (ref "IC6") (pin "U5") (pinfunction "PL77B_U5") (pintype "bidirectional"))
    )
    (net (code "237") (name "/SLOT7.LVDS_6_P") (class "Default")
      (node (ref "IC6") (pin "V4") (pinfunction "PL77A_V4") (pintype "bidirectional"))
    )
    (net (code "238") (name "/SLOT7.LVDS_7_N") (class "Default")
      (node (ref "IC6") (pin "V6") (pinfunction "PL80B_V6") (pintype "bidirectional"))
    )
    (net (code "239") (name "/SLOT7.LVDS_7_P") (class "Default")
      (node (ref "IC6") (pin "W4") (pinfunction "PL80A_W4") (pintype "bidirectional"))
    )
    (net (code "240") (name "/SLOT7.LVDS_8_N") (class "Default")
      (node (ref "R25") (pin "1") (pinfunction "1_1") (pintype "passive"))
      (node (ref "R27") (pin "2") (pinfunction "2_2") (pintype "passive"))
    )
    (net (code "241") (name "/SLOT7.LVDS_8_P") (class "Default")
      (node (ref "R24") (pin "2") (pinfunction "2_2") (pintype "passive"))
      (node (ref "R25") (pin "2") (pinfunction "2_2") (pintype "passive"))
    )
    (net (code "242") (name "/SLOT7.LVDS_9_N") (class "Default")
      (node (ref "R54") (pin "1") (pinfunction "1_1") (pintype "passive"))
      (node (ref "R57") (pin "2") (pinfunction "2_2") (pintype "passive"))
    )
    (net (code "243") (name "/SLOT7.LVDS_9_P") (class "Default")
      (node (ref "R53") (pin "2") (pinfunction "2_2") (pintype "passive"))
      (node (ref "R54") (pin "2") (pinfunction "2_2") (pintype "passive"))
    )
    (net (code "244") (name "/SLOT7.LVDS_10_N") (class "Default")
      (node (ref "R34") (pin "1") (pinfunction "1_1") (pintype "passive"))
      (node (ref "R48") (pin "2") (pinfunction "2_2") (pintype "passive"))
    )
    (net (code "245") (name "/SLOT7.LVDS_10_P") (class "Default")
      (node (ref "R32") (pin "2") (pinfunction "2_2") (pintype "passive"))
      (node (ref "R34") (pin "2") (pinfunction "2_2") (pintype "passive"))
    )
    (net (code "246") (name "/SLOT7.LVDS_11_N") (class "Default")
      (node (ref "R81") (pin "1") (pinfunction "1_1") (pintype "passive"))
      (node (ref "R83") (pin "2") (pinfunction "2_2") (pintype "passive"))
    )
    (net (code "247") (name "/SLOT7.LVDS_11_P") (class "Default")
      (node (ref "R80") (pin "2") (pinfunction "2_2") (pintype "passive"))
      (node (ref "R81") (pin "2") (pinfunction "2_2") (pintype "passive"))
    )
    (net (code "248") (name "/SLOT7.LVDS_12_N") (class "Default")
      (node (ref "R64") (pin "1") (pinfunction "1_1") (pintype "passive"))
      (node (ref "R66") (pin "2") (pinfunction "2_2") (pintype "passive"))
    )
    (net (code "249") (name "/SLOT7.LVDS_12_P") (class "Default")
      (node (ref "R63") (pin "2") (pinfunction "2_2") (pintype "passive"))
      (node (ref "R64") (pin "2") (pinfunction "2_2") (pintype "passive"))
    )
    (net (code "250") (name "/SLOT7.LVDS_13_N") (class "Default")
      (node (ref "R164") (pin "1") (pinfunction "1_1") (pintype "passive"))
      (node (ref "R165") (pin "2") (pinfunction "2_2") (pintype "passive"))
    )
    (net (code "251") (name "/SLOT7.LVDS_13_P") (class "Default")
      (node (ref "R163") (pin "2") (pinfunction "2_2") (pintype "passive"))
      (node (ref "R164") (pin "2") (pinfunction "2_2") (pintype "passive"))
    )
    (net (code "252") (name "/SLOT7.LVDS_14_N") (class "Default")
      (node (ref "R87") (pin "1") (pinfunction "1_1") (pintype "passive"))
      (node (ref "R89") (pin "2") (pinfunction "2_2") (pintype "passive"))
    )
    (net (code "253") (name "/SLOT7.LVDS_14_P") (class "Default")
      (node (ref "R86") (pin "2") (pinfunction "2_2") (pintype "passive"))
      (node (ref "R87") (pin "2") (pinfunction "2_2") (pintype "passive"))
    )
    (net (code "254") (name "/SLOT7.LVDS_15_N") (class "Default")
      (node (ref "R116") (pin "1") (pinfunction "1_1") (pintype "passive"))
      (node (ref "R119") (pin "2") (pinfunction "2_2") (pintype "passive"))
    )
    (net (code "255") (name "/SLOT7.LVDS_15_P") (class "Default")
      (node (ref "R115") (pin "2") (pinfunction "2_2") (pintype "passive"))
      (node (ref "R116") (pin "2") (pinfunction "2_2") (pintype "passive"))
    )
    (net (code "256") (name "/SLOT7.LVDSr0_N") (class "Default")
      (node (ref "IC6") (pin "L22") (pinfunction "PR38D_L22") (pintype "bidirectional"))
      (node (ref "R275") (pin "1") (pinfunction "1_1") (pintype "passive"))
    )
    (net (code "257") (name "/SLOT7.LVDSr0_P") (class "Default")
      (node (ref "IC6") (pin "H23") (pinfunction "PR38C_H23") (pintype "bidirectional"))
      (node (ref "R273") (pin "1") (pinfunction "1_1") (pintype "passive"))
    )
    (net (code "258") (name "/SLOT7.LVDSr1_N") (class "Default")
      (node (ref "IC6") (pin "B24") (pinfunction "PR14D_B24") (pintype "bidirectional"))
      (node (ref "R252") (pin "1") (pinfunction "1_1") (pintype "passive"))
    )
    (net (code "259") (name "/SLOT7.LVDSr1_P") (class "Default")
      (node (ref "IC6") (pin "B26") (pinfunction "PR14C_B26") (pintype "bidirectional"))
      (node (ref "R250") (pin "1") (pinfunction "1_1") (pintype "passive"))
    )
    (net (code "260") (name "/SLOT7.LVDSr3_N") (class "Default")
      (node (ref "IC6") (pin "L5") (pinfunction "PL38D_L5") (pintype "bidirectional"))
      (node (ref "R159") (pin "1") (pinfunction "1_1") (pintype "passive"))
    )
    (net (code "261") (name "/SLOT7.LVDSr3_P") (class "Default")
      (node (ref "IC6") (pin "H4") (pinfunction "PL38C_H4") (pintype "bidirectional"))
      (node (ref "R157") (pin "1") (pinfunction "1_1") (pintype "passive"))
    )
    (net (code "262") (name "/SLOT7.LVDSr8_N") (class "Default")
      (node (ref "IC6") (pin "H1") (pinfunction "PL47D/PCLKC6_0_H1") (pintype "bidirectional"))
      (node (ref "R27") (pin "1") (pinfunction "1_1") (pintype "passive"))
    )
    (net (code "263") (name "/SLOT7.LVDSr8_P") (class "Default")
      (node (ref "IC6") (pin "H2") (pinfunction "PL47C/PCLKT6_0_H2") (pintype "bidirectional"))
      (node (ref "R24") (pin "1") (pinfunction "1_1") (pintype "passive"))
    )
    (net (code "264") (name "/SLOT7.LVDSr9_N") (class "Default")
      (node (ref "IC6") (pin "L1") (pinfunction "PL53D_L1") (pintype "bidirectional"))
      (node (ref "R57") (pin "1") (pinfunction "1_1") (pintype "passive"))
    )
    (net (code "265") (name "/SLOT7.LVDSr9_P") (class "Default")
      (node (ref "IC6") (pin "K1") (pinfunction "PL53C_K1") (pintype "bidirectional"))
      (node (ref "R53") (pin "1") (pinfunction "1_1") (pintype "passive"))
    )
    (net (code "266") (name "/SLOT7.LVDSr10_N") (class "Default")
      (node (ref "IC6") (pin "M4") (pinfunction "PL41D_M4") (pintype "bidirectional"))
      (node (ref "R48") (pin "1") (pinfunction "1_1") (pintype "passive"))
    )
    (net (code "267") (name "/SLOT7.LVDSr10_P") (class "Default")
      (node (ref "IC6") (pin "M6") (pinfunction "PL41C/GR_PCLK7_0_M6") (pintype "bidirectional"))
      (node (ref "R32") (pin "1") (pinfunction "1_1") (pintype "passive"))
    )
    (net (code "268") (name "/SLOT7.LVDSr11_N") (class "Default")
      (node (ref "IC6") (pin "N5") (pinfunction "PL44D/PCLKC7_0_N5") (pintype "bidirectional"))
      (node (ref "R83") (pin "1") (pinfunction "1_1") (pintype "passive"))
    )
    (net (code "269") (name "/SLOT7.LVDSr11_P") (class "Default")
      (node (ref "IC6") (pin "N6") (pinfunction "PL44C/PCLKT7_0_N6") (pintype "bidirectional"))
      (node (ref "R80") (pin "1") (pinfunction "1_1") (pintype "passive"))
    )
    (net (code "270") (name "/SLOT7.LVDSr12_N") (class "Default")
      (node (ref "IC6") (pin "N4") (pinfunction "PL71D_N4") (pintype "bidirectional"))
      (node (ref "R66") (pin "1") (pinfunction "1_1") (pintype "passive"))
    )
    (net (code "271") (name "/SLOT7.LVDSr12_P") (class "Default")
      (node (ref "IC6") (pin "P6") (pinfunction "PL71C_P6") (pintype "bidirectional"))
      (node (ref "R63") (pin "1") (pinfunction "1_1") (pintype "passive"))
    )
    (net (code "272") (name "/SLOT7.LVDSr13_N") (class "Default")
      (node (ref "IC6") (pin "T4") (pinfunction "PL74D_T4") (pintype "bidirectional"))
      (node (ref "R165") (pin "1") (pinfunction "1_1") (pintype "passive"))
    )
    (net (code "273") (name "/SLOT7.LVDSr13_P") (class "Default")
      (node (ref "IC6") (pin "R6") (pinfunction "PL74C_R6") (pintype "bidirectional"))
      (node (ref "R163") (pin "1") (pinfunction "1_1") (pintype "passive"))
    )
    (net (code "274") (name "/SLOT7.LVDSr14_N") (class "Default")
      (node (ref "IC6") (pin "P3") (pinfunction "PL83D_P3") (pintype "bidirectional"))
      (node (ref "R89") (pin "1") (pinfunction "1_1") (pintype "passive"))
    )
    (net (code "275") (name "/SLOT7.LVDSr14_P") (class "Default")
      (node (ref "IC6") (pin "R3") (pinfunction "PL83C_R3") (pintype "bidirectional"))
      (node (ref "R86") (pin "1") (pinfunction "1_1") (pintype "passive"))
    )
    (net (code "276") (name "/SLOT7.LVDSr15_N") (class "Default")
      (node (ref "IC6") (pin "T26") (pinfunction "PR89D_T26") (pintype "bidirectional"))
      (node (ref "R119") (pin "1") (pinfunction "1_1") (pintype "passive"))
    )
    (net (code "277") (name "/SLOT7.LVDSr15_P") (class "Default")
      (node (ref "IC6") (pin "U26") (pinfunction "PR89C_U26") (pintype "bidirectional"))
      (node (ref "R115") (pin "1") (pinfunction "1_1") (pintype "passive"))
    )
    (net (code "278") (name "/SLOT8.LVDS_0_N") (class "Default")
      (node (ref "R257") (pin "1") (pinfunction "1_1") (pintype "passive"))
      (node (ref "R258") (pin "2") (pinfunction "2_2") (pintype "passive"))
    )
    (net (code "279") (name "/SLOT8.LVDS_0_P") (class "Default")
      (node (ref "R256") (pin "2") (pinfunction "2_2") (pintype "passive"))
      (node (ref "R257") (pin "2") (pinfunction "2_2") (pintype "passive"))
    )
    (net (code "280") (name "/SLOT8.LVDS_1_N") (class "Default")
      (node (ref "R62") (pin "1") (pinfunction "1_1") (pintype "passive"))
      (node (ref "R65") (pin "2") (pinfunction "2_2") (pintype "passive"))
    )
    (net (code "281") (name "/SLOT8.LVDS_1_P") (class "Default")
      (node (ref "R61") (pin "2") (pinfunction "2_2") (pintype "passive"))
      (node (ref "R62") (pin "2") (pinfunction "2_2") (pintype "passive"))
    )
    (net (code "282") (name "/SLOT8.LVDS_2_N") (class "Default")
      (node (ref "IC6") (pin "M26") (pinfunction "PR53B_M26") (pintype "bidirectional"))
    )
    (net (code "283") (name "/SLOT8.LVDS_2_P") (class "Default")
      (node (ref "IC6") (pin "L25") (pinfunction "PR53A_L25") (pintype "bidirectional"))
    )
    (net (code "284") (name "/SLOT8.LVDS_3_N") (class "Default")
      (node (ref "R146") (pin "1") (pinfunction "1_1") (pintype "passive"))
      (node (ref "R147") (pin "2") (pinfunction "2_2") (pintype "passive"))
    )
    (net (code "285") (name "/SLOT8.LVDS_3_P") (class "Default")
      (node (ref "R145") (pin "2") (pinfunction "2_2") (pintype "passive"))
      (node (ref "R146") (pin "2") (pinfunction "2_2") (pintype "passive"))
    )
    (net (code "286") (name "/SLOT8.LVDS_4_N") (class "Default")
      (node (ref "IC6") (pin "F4") (pinfunction "PL35B_F4") (pintype "bidirectional"))
    )
    (net (code "287") (name "/SLOT8.LVDS_4_P") (class "Default")
      (node (ref "IC6") (pin "F5") (pinfunction "PL35A_F5") (pintype "bidirectional"))
    )
    (net (code "288") (name "/SLOT8.LVDS_5_N") (class "Default")
      (node (ref "IC6") (pin "U2") (pinfunction "PL89B_U2") (pintype "bidirectional"))
    )
    (net (code "289") (name "/SLOT8.LVDS_5_P") (class "Default")
      (node (ref "IC6") (pin "V1") (pinfunction "PL89A_V1") (pintype "bidirectional"))
    )
    (net (code "290") (name "/SLOT8.LVDS_6_N") (class "Default")
      (node (ref "IC6") (pin "N2") (pinfunction "PL56B/VREF1_6_N2") (pintype "bidirectional"))
    )
    (net (code "291") (name "/SLOT8.LVDS_6_P") (class "Default")
      (node (ref "IC6") (pin "N1") (pinfunction "PL56A_N1") (pintype "bidirectional"))
    )
    (net (code "292") (name "/SLOT8.LVDS_7_N") (class "Default")
      (node (ref "IC6") (pin "W1") (pinfunction "PL92B_W1") (pintype "bidirectional"))
    )
    (net (code "293") (name "/SLOT8.LVDS_7_P") (class "Default")
      (node (ref "IC6") (pin "V3") (pinfunction "PL92A_V3") (pintype "bidirectional"))
    )
    (net (code "294") (name "/SLOT8.LVDS_8_N") (class "Default")
      (node (ref "R112") (pin "1") (pinfunction "1_1") (pintype "passive"))
      (node (ref "R114") (pin "2") (pinfunction "2_2") (pintype "passive"))
    )
    (net (code "295") (name "/SLOT8.LVDS_8_P") (class "Default")
      (node (ref "R111") (pin "2") (pinfunction "2_2") (pintype "passive"))
      (node (ref "R112") (pin "2") (pinfunction "2_2") (pintype "passive"))
    )
    (net (code "296") (name "/SLOT8.LVDS_9_N") (class "Default")
      (node (ref "R70") (pin "1") (pinfunction "1_1") (pintype "passive"))
      (node (ref "R72") (pin "2") (pinfunction "2_2") (pintype "passive"))
    )
    (net (code "297") (name "/SLOT8.LVDS_9_P") (class "Default")
      (node (ref "R69") (pin "2") (pinfunction "2_2") (pintype "passive"))
      (node (ref "R70") (pin "2") (pinfunction "2_2") (pintype "passive"))
    )
    (net (code "298") (name "/SLOT8.LVDS_10_N") (class "Default")
      (node (ref "R161") (pin "1") (pinfunction "1_1") (pintype "passive"))
      (node (ref "R162") (pin "2") (pinfunction "2_2") (pintype "passive"))
    )
    (net (code "299") (name "/SLOT8.LVDS_10_P") (class "Default")
      (node (ref "R160") (pin "2") (pinfunction "2_2") (pintype "passive"))
      (node (ref "R161") (pin "2") (pinfunction "2_2") (pintype "passive"))
    )
    (net (code "300") (name "/SLOT8.LVDS_11_N") (class "Default")
      (node (ref "R106") (pin "1") (pinfunction "1_1") (pintype "passive"))
      (node (ref "R108") (pin "2") (pinfunction "2_2") (pintype "passive"))
    )
    (net (code "301") (name "/SLOT8.LVDS_11_P") (class "Default")
      (node (ref "R105") (pin "2") (pinfunction "2_2") (pintype "passive"))
      (node (ref "R106") (pin "2") (pinfunction "2_2") (pintype "passive"))
    )
    (net (code "302") (name "/SLOT8.LVDS_12_N") (class "Default")
      (node (ref "R118") (pin "1") (pinfunction "1_1") (pintype "passive"))
      (node (ref "R120") (pin "2") (pinfunction "2_2") (pintype "passive"))
    )
    (net (code "303") (name "/SLOT8.LVDS_12_P") (class "Default")
      (node (ref "R117") (pin "2") (pinfunction "2_2") (pintype "passive"))
      (node (ref "R118") (pin "2") (pinfunction "2_2") (pintype "passive"))
    )
    (net (code "304") (name "/SLOT8.LVDS_13_N") (class "Default")
      (node (ref "R124") (pin "1") (pinfunction "1_1") (pintype "passive"))
      (node (ref "R130") (pin "2") (pinfunction "2_2") (pintype "passive"))
    )
    (net (code "305") (name "/SLOT8.LVDS_13_P") (class "Default")
      (node (ref "R123") (pin "2") (pinfunction "2_2") (pintype "passive"))
      (node (ref "R124") (pin "2") (pinfunction "2_2") (pintype "passive"))
    )
    (net (code "306") (name "/SLOT8.LVDS_14_N") (class "Default")
      (node (ref "R100") (pin "1") (pinfunction "1_1") (pintype "passive"))
      (node (ref "R102") (pin "2") (pinfunction "2_2") (pintype "passive"))
    )
    (net (code "307") (name "/SLOT8.LVDS_14_P") (class "Default")
      (node (ref "R100") (pin "2") (pinfunction "2_2") (pintype "passive"))
      (node (ref "R94") (pin "2") (pinfunction "2_2") (pintype "passive"))
    )
    (net (code "308") (name "/SLOT8.LVDS_15_N") (class "Default")
      (node (ref "R110") (pin "1") (pinfunction "1_1") (pintype "passive"))
      (node (ref "R113") (pin "2") (pinfunction "2_2") (pintype "passive"))
    )
    (net (code "309") (name "/SLOT8.LVDS_15_P") (class "Default")
      (node (ref "R109") (pin "2") (pinfunction "2_2") (pintype "passive"))
      (node (ref "R110") (pin "2") (pinfunction "2_2") (pintype "passive"))
    )
    (net (code "310") (name "/SLOT8.LVDSr0_N") (class "Default")
      (node (ref "IC6") (pin "F24") (pinfunction "PR20D_F24") (pintype "bidirectional"))
      (node (ref "R258") (pin "1") (pinfunction "1_1") (pintype "passive"))
    )
    (net (code "311") (name "/SLOT8.LVDSr0_P") (class "Default")
      (node (ref "IC6") (pin "E23") (pinfunction "PR20C_E23") (pintype "bidirectional"))
      (node (ref "R256") (pin "1") (pinfunction "1_1") (pintype "passive"))
    )
    (net (code "312") (name "/SLOT8.LVDSr1_N") (class "Default")
      (node (ref "IC6") (pin "M24") (pinfunction "PR56D_M24") (pintype "bidirectional"))
      (node (ref "R65") (pin "1") (pinfunction "1_1") (pintype "passive"))
    )
    (net (code "313") (name "/SLOT8.LVDSr1_P") (class "Default")
      (node (ref "IC6") (pin "N24") (pinfunction "PR56C_N24") (pintype "bidirectional"))
      (node (ref "R61") (pin "1") (pinfunction "1_1") (pintype "passive"))
    )
    (net (code "314") (name "/SLOT8.LVDSr3_N") (class "Default")
      (node (ref "IC6") (pin "B3") (pinfunction "PL14D_B3") (pintype "bidirectional"))
      (node (ref "R147") (pin "1") (pinfunction "1_1") (pintype "passive"))
    )
    (net (code "315") (name "/SLOT8.LVDSr3_P") (class "Default")
      (node (ref "IC6") (pin "B1") (pinfunction "PL14C_B1") (pintype "bidirectional"))
      (node (ref "R145") (pin "1") (pinfunction "1_1") (pintype "passive"))
    )
    (net (code "316") (name "/SLOT8.LVDSr8_N") (class "Default")
      (node (ref "IC6") (pin "R1") (pinfunction "PL86D_R1") (pintype "bidirectional"))
      (node (ref "R114") (pin "1") (pinfunction "1_1") (pintype "passive"))
    )
    (net (code "317") (name "/SLOT8.LVDSr8_P") (class "Default")
      (node (ref "IC6") (pin "T2") (pinfunction "PL86C_T2") (pintype "bidirectional"))
      (node (ref "R111") (pin "1") (pinfunction "1_1") (pintype "passive"))
    )
    (net (code "318") (name "/SLOT8.LVDSr9_N") (class "Default")
      (node (ref "IC6") (pin "M3") (pinfunction "PL56D_M3") (pintype "bidirectional"))
      (node (ref "R72") (pin "1") (pinfunction "1_1") (pintype "passive"))
    )
    (net (code "319") (name "/SLOT8.LVDSr9_P") (class "Default")
      (node (ref "IC6") (pin "N3") (pinfunction "PL56C_N3") (pintype "bidirectional"))
      (node (ref "R69") (pin "1") (pinfunction "1_1") (pintype "passive"))
    )
    (net (code "320") (name "/SLOT8.LVDSr10_N") (class "Default")
      (node (ref "IC6") (pin "L3") (pinfunction "PL50D_L3") (pintype "bidirectional"))
      (node (ref "R162") (pin "1") (pinfunction "1_1") (pintype "passive"))
    )
    (net (code "321") (name "/SLOT8.LVDSr10_P") (class "Default")
      (node (ref "IC6") (pin "K3") (pinfunction "PL50C/GR_PCLK6_1_K3") (pintype "bidirectional"))
      (node (ref "R160") (pin "1") (pinfunction "1_1") (pintype "passive"))
    )
    (net (code "322") (name "/SLOT8.LVDSr11_N") (class "Default")
      (node (ref "IC6") (pin "U4") (pinfunction "PL77D_U4") (pintype "bidirectional"))
      (node (ref "R108") (pin "1") (pinfunction "1_1") (pintype "passive"))
    )
    (net (code "323") (name "/SLOT8.LVDSr11_P") (class "Default")
      (node (ref "IC6") (pin "U6") (pinfunction "PL77C_U6") (pintype "bidirectional"))
      (node (ref "R105") (pin "1") (pinfunction "1_1") (pintype "passive"))
    )
    (net (code "324") (name "/SLOT8.LVDSr12_N") (class "Default")
      (node (ref "IC6") (pin "T1") (pinfunction "PL89D_T1") (pintype "bidirectional"))
      (node (ref "R120") (pin "1") (pinfunction "1_1") (pintype "passive"))
    )
    (net (code "325") (name "/SLOT8.LVDSr12_P") (class "Default")
      (node (ref "IC6") (pin "U1") (pinfunction "PL89C_U1") (pintype "bidirectional"))
      (node (ref "R117") (pin "1") (pinfunction "1_1") (pintype "passive"))
    )
    (net (code "326") (name "/SLOT8.LVDSr13_N") (class "Default")
      (node (ref "IC6") (pin "W3") (pinfunction "PL92D/LLC_GPLL0C_IN_W3") (pintype "bidirectional"))
      (node (ref "R130") (pin "1") (pinfunction "1_1") (pintype "passive"))
    )
    (net (code "327") (name "/SLOT8.LVDSr13_P") (class "Default")
      (node (ref "IC6") (pin "W2") (pinfunction "PL92C/LLC_GPLL0T_IN_W2") (pintype "bidirectional"))
      (node (ref "R123") (pin "1") (pinfunction "1_1") (pintype "passive"))
    )
    (net (code "328") (name "/SLOT8.LVDSr14_N") (class "Default")
      (node (ref "IC6") (pin "W6") (pinfunction "PL80D_W6") (pintype "bidirectional"))
      (node (ref "R102") (pin "1") (pinfunction "1_1") (pintype "passive"))
    )
    (net (code "329") (name "/SLOT8.LVDSr14_P") (class "Default")
      (node (ref "IC6") (pin "W5") (pinfunction "PL80C_W5") (pintype "bidirectional"))
      (node (ref "R94") (pin "1") (pinfunction "1_1") (pintype "passive"))
    )
    (net (code "330") (name "/SLOT8.LVDSr15_N") (class "Default")
      (node (ref "IC6") (pin "R26") (pinfunction "PR86D_R26") (pintype "bidirectional"))
      (node (ref "R113") (pin "1") (pinfunction "1_1") (pintype "passive"))
    )
    (net (code "331") (name "/SLOT8.LVDSr15_P") (class "Default")
      (node (ref "IC6") (pin "T25") (pinfunction "PR86C_T25") (pintype "bidirectional"))
      (node (ref "R109") (pin "1") (pinfunction "1_1") (pintype "passive"))
    )
    (net (code "332") (name "/SPI1_MISO") (class "Default")
      (node (ref "IC6") (pin "E16") (pinfunction "PT80B_E16") (pintype "bidirectional"))
    )
    (net (code "333") (name "/SPI1_MOSI") (class "Default")
      (node (ref "IC6") (pin "E19") (pinfunction "PT103A_E19") (pintype "bidirectional"))
    )
    (net (code "334") (name "/SPI1_NSS") (class "Default")
      (node (ref "IC6") (pin "D21") (pinfunction "PT114A_D21") (pintype "bidirectional"))
    )
    (net (code "335") (name "/SPI1_SCK") (class "Default")
      (node (ref "IC6") (pin "C13") (pinfunction "PT74A/GR_PCLK1_0_C13") (pintype "bidirectional"))
    )
    (net (code "336") (name "/SPI2_MISO") (class "Default")
      (node (ref "IC6") (pin "AC1") (pinfunction "PB6A/D5/MISO2/IO5_AC1") (pintype "bidirectional"))
    )
    (net (code "337") (name "/SPI2_MOSI") (class "Default")
      (node (ref "IC6") (pin "AB2") (pinfunction "PB13A/SN/CSN_AB2") (pintype "bidirectional"))
    )
    (net (code "338") (name "/SPI2_NSS") (class "Default")
      (node (ref "IC6") (pin "D9") (pinfunction "PT51A_D9") (pintype "bidirectional"))
    )
    (net (code "339") (name "/SPI2_SCK") (class "Default")
      (node (ref "IC6") (pin "D13") (pinfunction "PT71A/PCLKT1_0_D13") (pintype "bidirectional"))
    )
    (net (code "340") (name "/SPI3_MISO") (class "Default")
      (node (ref "IC6") (pin "D16") (pinfunction "PT80A_D16") (pintype "bidirectional"))
    )
    (net (code "341") (name "/SPI3_MOSI") (class "Default")
      (node (ref "IC6") (pin "AA1") (pinfunction "PB4A/D7/IO7_AA1") (pintype "bidirectional"))
    )
    (net (code "342") (name "/SPI3_NSS") (class "Default")
      (node (ref "IC6") (pin "AB1") (pinfunction "PB4B/D6/IO6_AB1") (pintype "bidirectional"))
    )
    (net (code "343") (name "/SPI3_SCK") (class "Default")
      (node (ref "IC6") (pin "E13") (pinfunction "PT69A/PCLKT1_1_E13") (pintype "bidirectional"))
    )
    (net (code "344") (name "/SPI4_CLK") (class "Default")
      (node (ref "IC6") (pin "B11") (pinfunction "PT60B/GR_PCLK0_0_B11") (pintype "bidirectional"))
    )
    (net (code "345") (name "/SPI4_MISO") (class "Default")
      (node (ref "IC6") (pin "D11") (pinfunction "PT63B/PCLKC0_1_D11") (pintype "bidirectional"))
    )
    (net (code "346") (name "/SPI4_MOSI") (class "Default")
      (node (ref "IC6") (pin "E10") (pinfunction "PT54A_E10") (pintype "bidirectional"))
    )
    (net (code "347") (name "/SPI4_NSS") (class "Default")
      (node (ref "IC6") (pin "E8") (pinfunction "PT49A_E8") (pintype "bidirectional"))
    )
    (net (code "348") (name "/SPI5_MISO") (class "Default")
      (node (ref "IC6") (pin "AD1") (pinfunction "PB6B/D4/MOSI2/IO4_AD1") (pintype "bidirectional"))
    )
    (net (code "349") (name "/SPI5_MOSI") (class "Default")
      (node (ref "IC6") (pin "AC2") (pinfunction "PB13B/CS1N_AC2") (pintype "bidirectional"))
    )
    (net (code "350") (name "/SPI5_NSS") (class "Default")
      (node (ref "IC6") (pin "D8") (pinfunction "PT49B_D8") (pintype "bidirectional"))
    )
    (net (code "351") (name "/SPI5_SCK") (class "Default")
      (node (ref "IC6") (pin "A3") (pinfunction "PT4B/ULC_GPLL1C_IN_A3") (pintype "bidirectional"))
    )
    (net (code "352") (name "/SPI6_MISO") (class "Default")
      (node (ref "IC6") (pin "D18") (pinfunction "PT101B_D18") (pintype "bidirectional"))
    )
    (net (code "353") (name "/SPI6_MOSI") (class "Default")
      (node (ref "IC6") (pin "E17") (pinfunction "PT98B_E17") (pintype "bidirectional"))
    )
    (net (code "354") (name "/SPI6_NSS") (class "Default")
      (node (ref "IC6") (pin "E14") (pinfunction "PT69B/PCLKC1_1_E14") (pintype "bidirectional"))
    )
    (net (code "355") (name "/SPI6_SCK") (class "Default")
      (node (ref "IC6") (pin "A12") (pinfunction "PT65A/PCLKT0_0_A12") (pintype "bidirectional"))
    )
    (net (code "364") (name "GND") (class "Default")
      (node (ref "D13") (pin "2") (pinfunction "GND_2") (pintype "power_in"))
      (node (ref "D14") (pin "2") (pinfunction "GND_2") (pintype "power_in"))
      (node (ref "IC6") (pin "AD4") (pinfunction "CFG_2_AD4") (pintype "bidirectional"))
      (node (ref "IC6") (pin "AF4") (pinfunction "CFG_0_AF4") (pintype "bidirectional"))
    )
    (net (code "365") (name "Net-(IC6H-INITN)") (class "Default")
      (node (ref "B1") (pin "1") (pinfunction "1_1") (pintype "bidirectional"))
      (node (ref "IC6") (pin "AF3") (pinfunction "INITN_AF3") (pintype "bidirectional"))
      (node (ref "R229") (pin "1") (pinfunction "1_1") (pintype "passive"))
    )
    (net (code "366") (name "P3V3") (class "Default")
      (node (ref "D13") (pin "5") (pinfunction "VBUS_5") (pintype "power_in"))
      (node (ref "D14") (pin "5") (pinfunction "VBUS_5") (pintype "power_in"))
      (node (ref "IC6") (pin "AE4") (pinfunction "CFG_1_AE4") (pintype "bidirectional"))
      (node (ref "R229") (pin "2") (pinfunction "2_2") (pintype "passive"))
    )
    (net (code "367") (name "unconnected-(D13-I{slash}O4-Pad6)") (class "Default")
      (node (ref "D13") (pin "6") (pinfunction "I/O4_6") (pintype "bidirectional+no_connect"))
    )
    (net (code "368") (name "unconnected-(D14-I{slash}O1-Pad1)") (class "Default")
      (node (ref "D14") (pin "1") (pinfunction "I/O1_1") (pintype "bidirectional+no_connect"))
    )
    (net (code "369") (name "unconnected-(D14-I{slash}O2-Pad3)") (class "Default")
      (node (ref "D14") (pin "3") (pinfunction "I/O2_3") (pintype "bidirectional+no_connect"))
    )
    (net (code "370") (name "unconnected-(IC6E-PB112B-PadAA25)") (class "Default")
      (node (ref "IC6") (pin "AA25") (pinfunction "PB112B_AA25") (pintype "bidirectional"))
    )
  )
)
